# Z573_Holder_Mark1.net
KiCad netlist of a schematic drawn in EAGLE
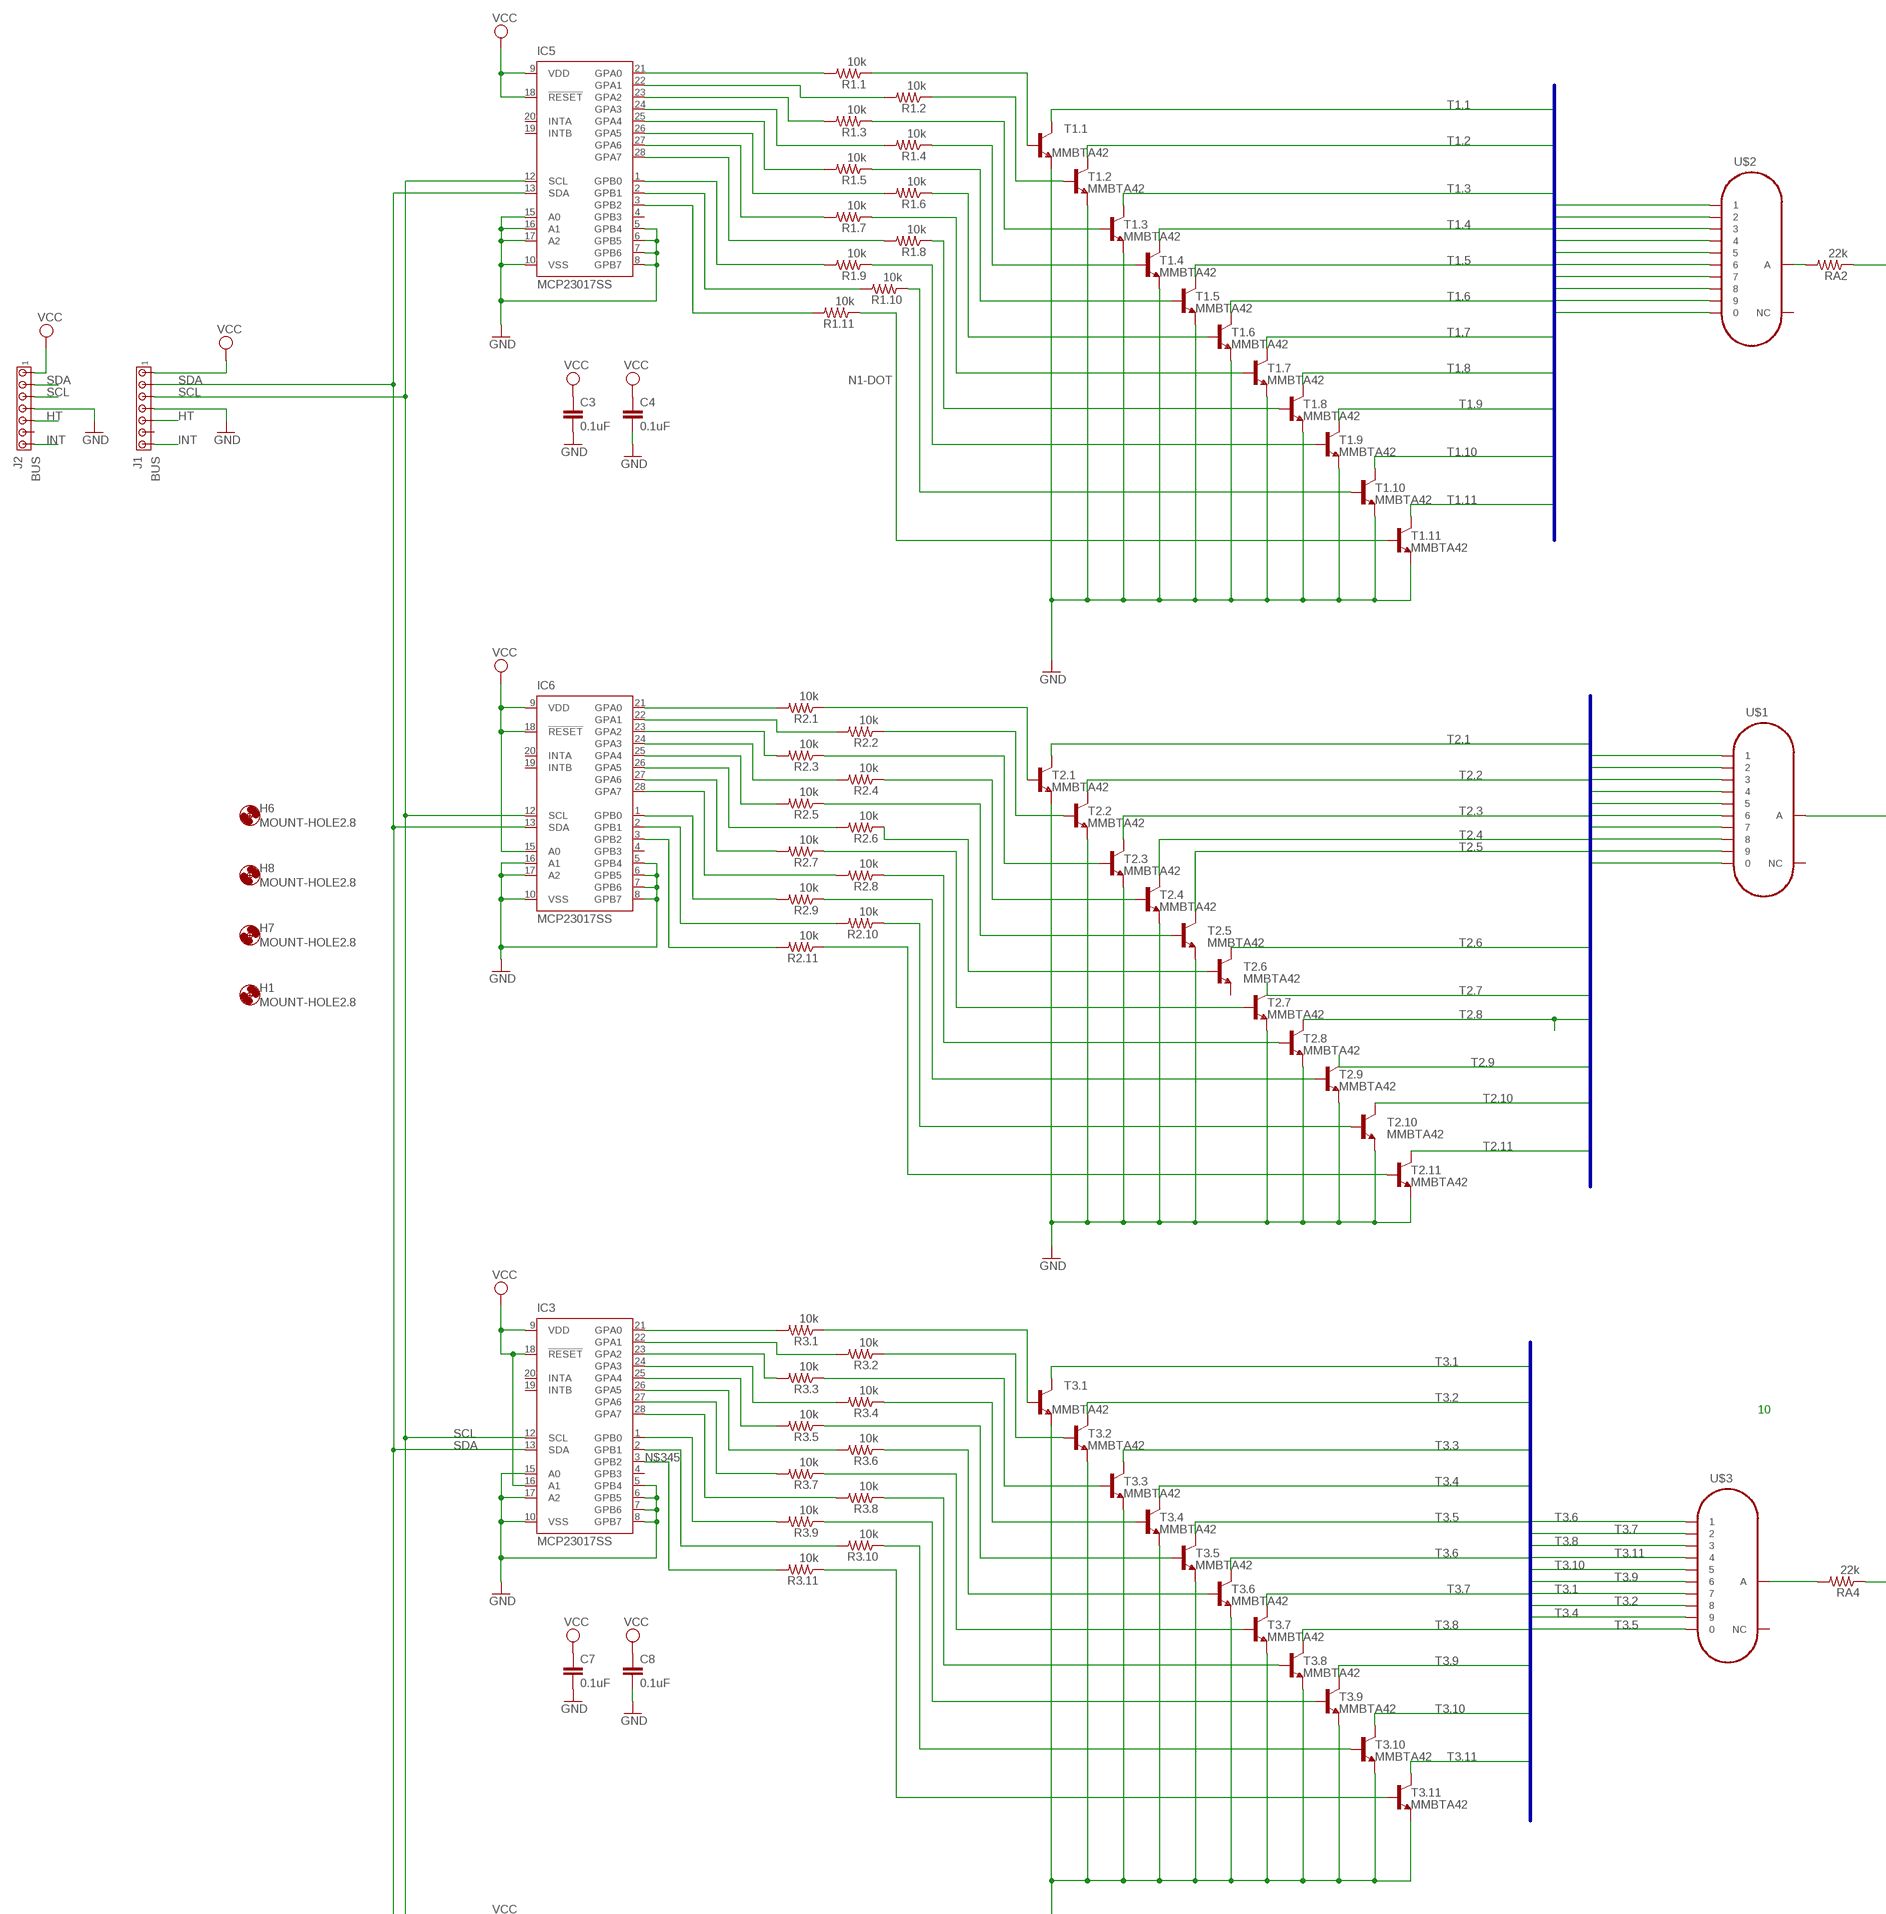
[diagram p0: schematic, sheet 1, part 1 of 3]
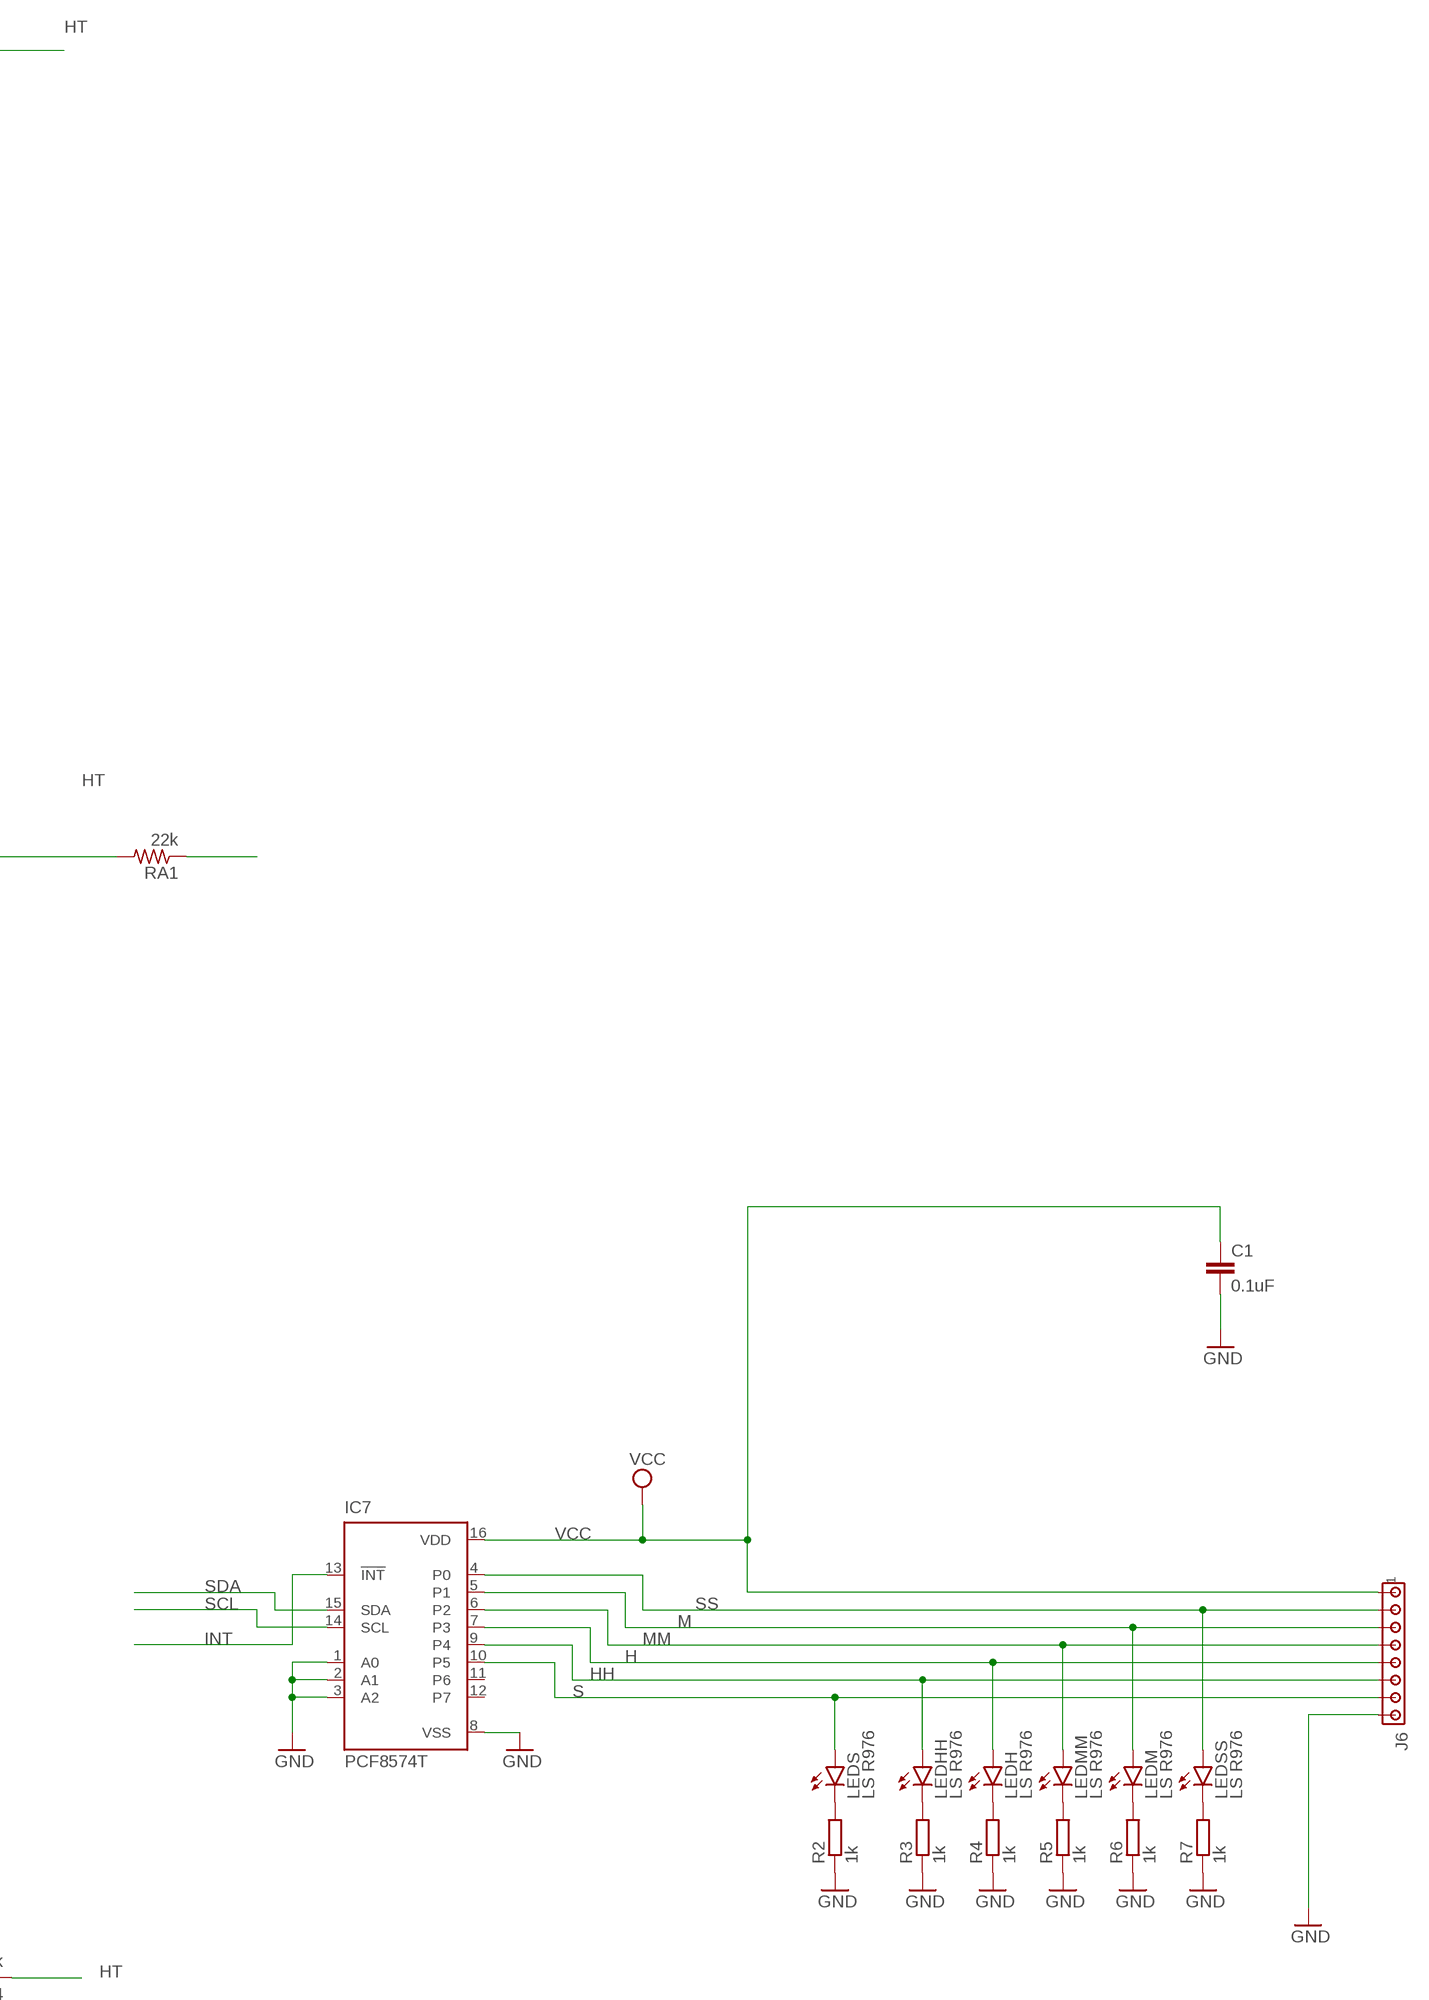
[diagram p1: schematic, sheet 1, part 2 of 3]
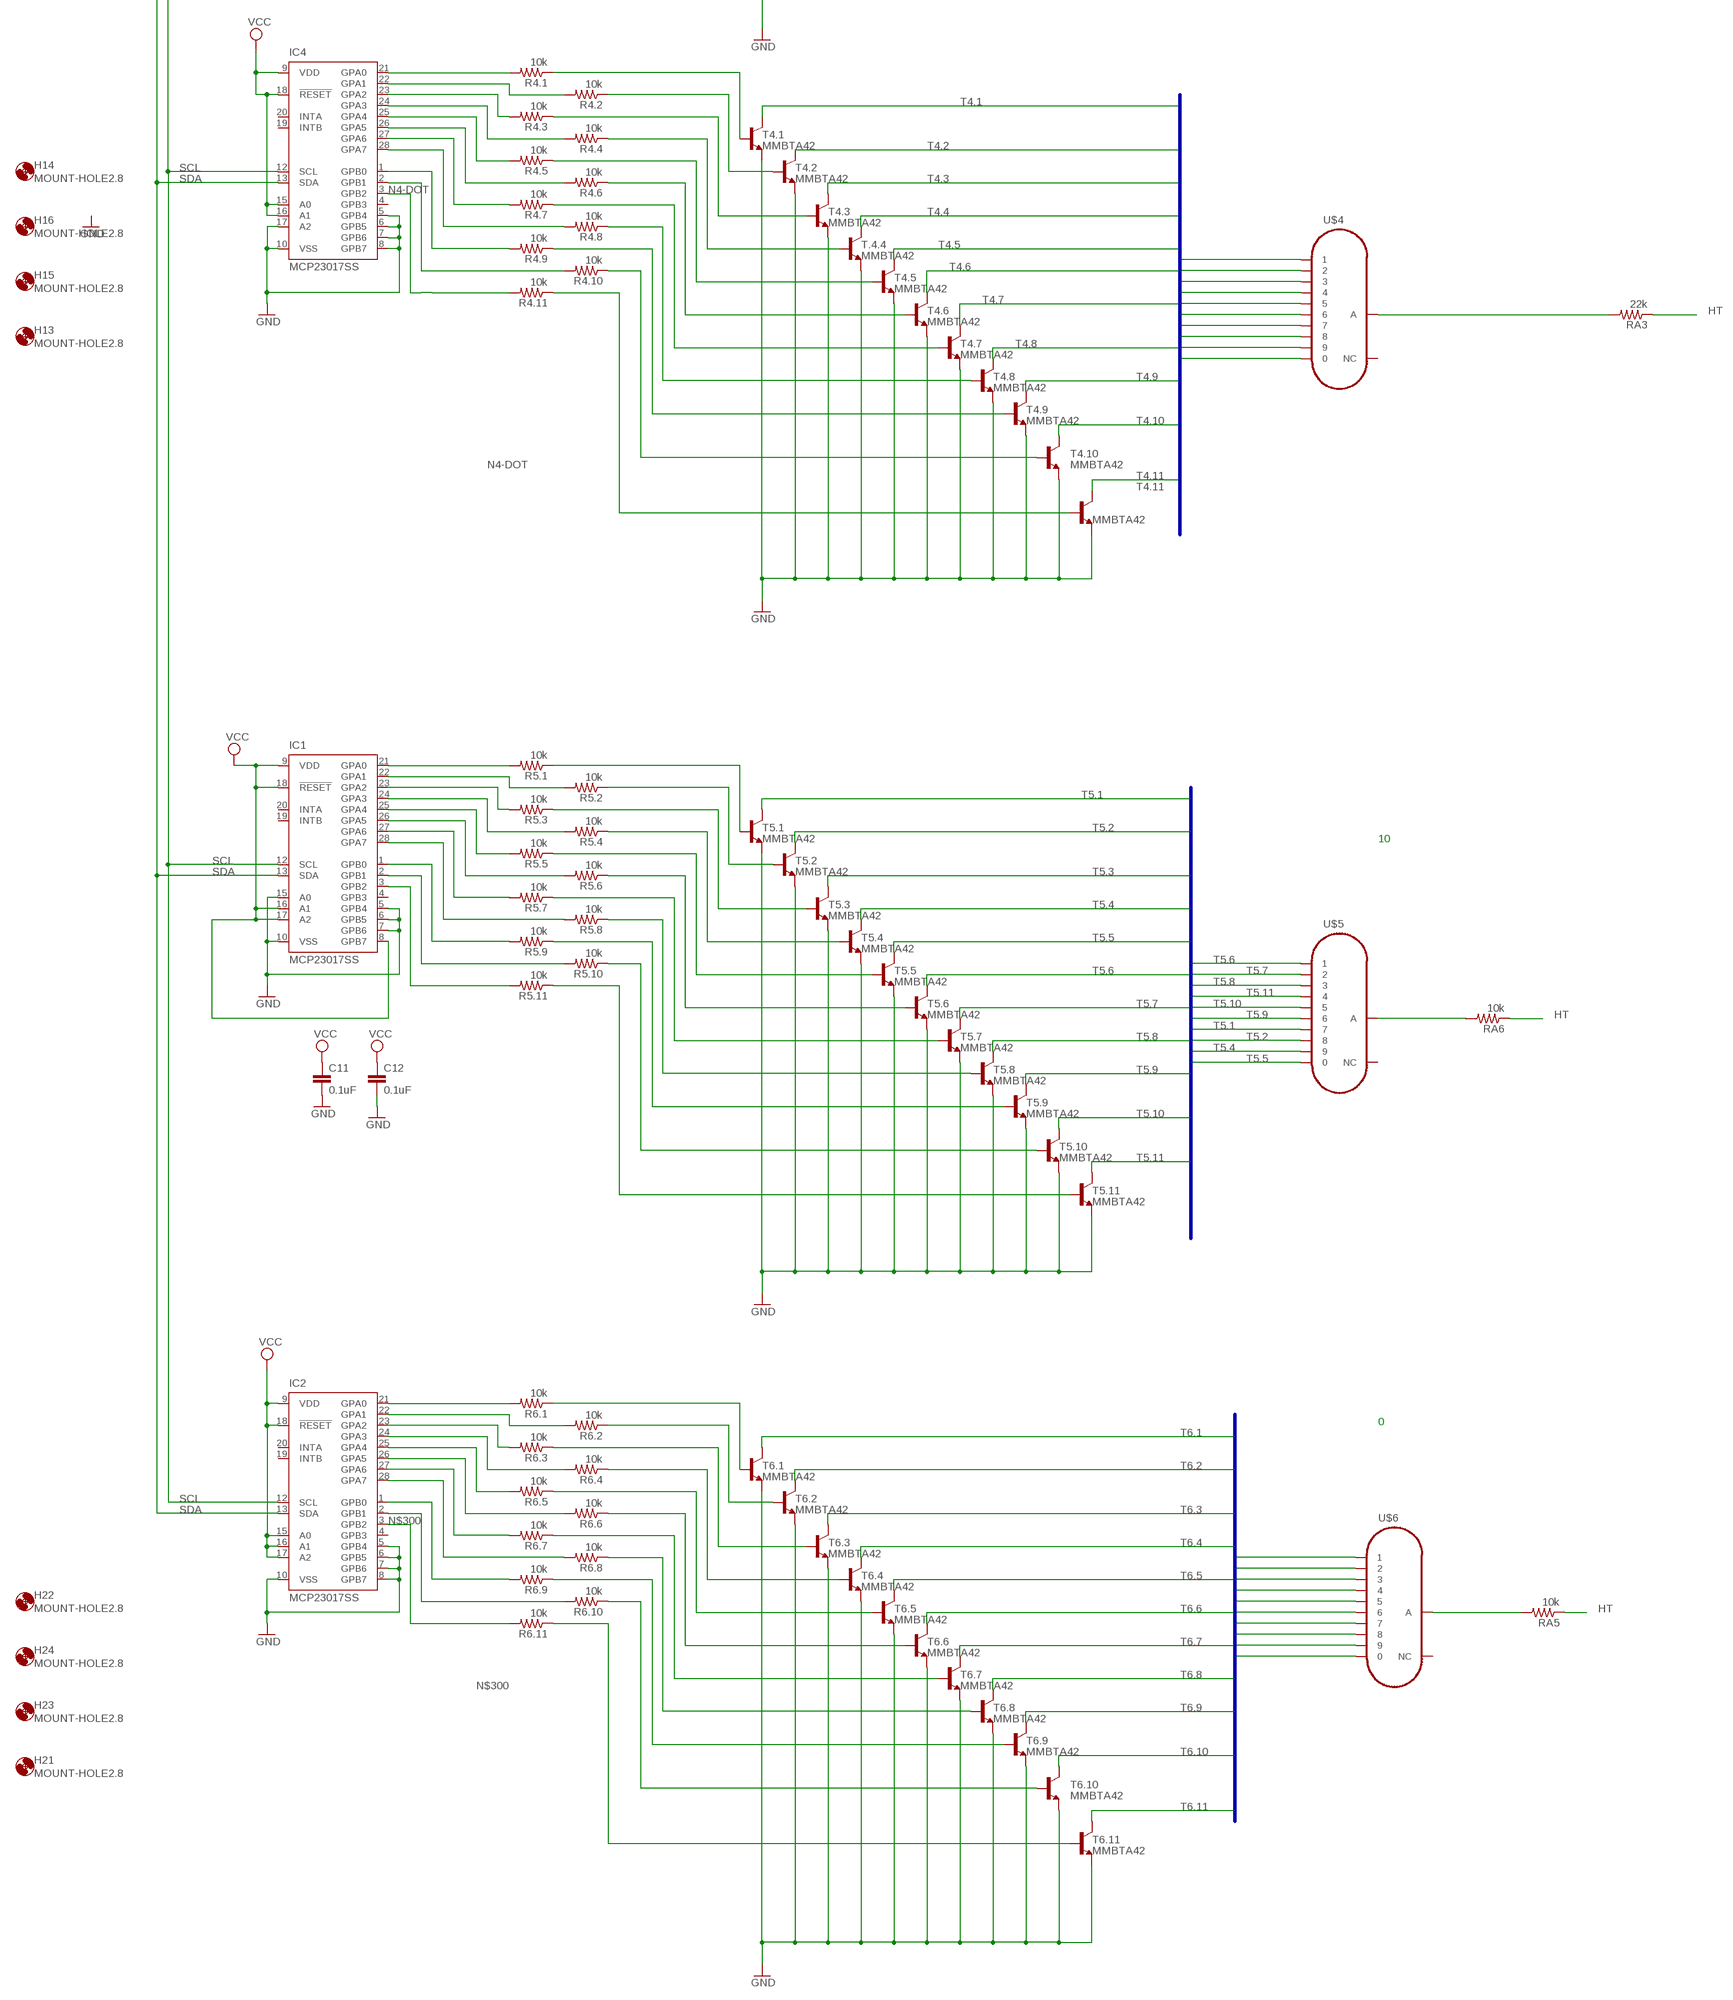
[diagram p2: schematic, sheet 1, part 3 of 3]

(export (version "E")
  (design (tool "Eeschema 10.0.6"))
  (components
    (comp (ref "C1")
      (value "0.1uF")
      (footprint "eagle-import:C0805")
      (libsource (lib "eagle-import") (part "C-EUC0805"))
    )
    (comp (ref "C3")
      (value "0.1uF")
      (footprint "eagle-import:C0805")
      (libsource (lib "eagle-import") (part "C-EUC0805"))
    )
    (comp (ref "C4")
      (value "0.1uF")
      (footprint "eagle-import:C0805")
      (libsource (lib "eagle-import") (part "C-EUC0805"))
    )
    (comp (ref "C7")
      (value "0.1uF")
      (footprint "eagle-import:C0805")
      (libsource (lib "eagle-import") (part "C-EUC0805"))
    )
    (comp (ref "C8")
      (value "0.1uF")
      (footprint "eagle-import:C0805")
      (libsource (lib "eagle-import") (part "C-EUC0805"))
    )
    (comp (ref "C11")
      (value "0.1uF")
      (footprint "eagle-import:C0805")
      (libsource (lib "eagle-import") (part "C-EUC0805"))
    )
    (comp (ref "C12")
      (value "0.1uF")
      (footprint "eagle-import:C0805")
      (libsource (lib "eagle-import") (part "C-EUC0805"))
    )
    (comp (ref "H1")
      (value "MOUNT-HOLE2.8")
      (footprint "eagle-import:2,8")
      (libsource (lib "eagle-import") (part "MOUNT-HOLE2.8"))
    )
    (comp (ref "H6")
      (value "MOUNT-HOLE2.8")
      (footprint "eagle-import:2,8")
      (libsource (lib "eagle-import") (part "MOUNT-HOLE2.8"))
    )
    (comp (ref "H7")
      (value "MOUNT-HOLE2.8")
      (footprint "eagle-import:2,8")
      (libsource (lib "eagle-import") (part "MOUNT-HOLE2.8"))
    )
    (comp (ref "H8")
      (value "MOUNT-HOLE2.8")
      (footprint "eagle-import:2,8")
      (libsource (lib "eagle-import") (part "MOUNT-HOLE2.8"))
    )
    (comp (ref "H13")
      (value "MOUNT-HOLE2.8")
      (footprint "eagle-import:2,8")
      (libsource (lib "eagle-import") (part "MOUNT-HOLE2.8"))
    )
    (comp (ref "H14")
      (value "MOUNT-HOLE2.8")
      (footprint "eagle-import:2,8")
      (libsource (lib "eagle-import") (part "MOUNT-HOLE2.8"))
    )
    (comp (ref "H15")
      (value "MOUNT-HOLE2.8")
      (footprint "eagle-import:2,8")
      (libsource (lib "eagle-import") (part "MOUNT-HOLE2.8"))
    )
    (comp (ref "H16")
      (value "MOUNT-HOLE2.8")
      (footprint "eagle-import:2,8")
      (libsource (lib "eagle-import") (part "MOUNT-HOLE2.8"))
    )
    (comp (ref "H21")
      (value "MOUNT-HOLE2.8")
      (footprint "eagle-import:2,8")
      (libsource (lib "eagle-import") (part "MOUNT-HOLE2.8"))
    )
    (comp (ref "H22")
      (value "MOUNT-HOLE2.8")
      (footprint "eagle-import:2,8")
      (libsource (lib "eagle-import") (part "MOUNT-HOLE2.8"))
    )
    (comp (ref "H23")
      (value "MOUNT-HOLE2.8")
      (footprint "eagle-import:2,8")
      (libsource (lib "eagle-import") (part "MOUNT-HOLE2.8"))
    )
    (comp (ref "H24")
      (value "MOUNT-HOLE2.8")
      (footprint "eagle-import:2,8")
      (libsource (lib "eagle-import") (part "MOUNT-HOLE2.8"))
    )
    (comp (ref "IC1")
      (value "MCP23017SS")
      (footprint "eagle-import:SSOP28")
      (libsource (lib "eagle-import") (part "MCP23017SS"))
    )
    (comp (ref "IC2")
      (value "MCP23017SS")
      (footprint "eagle-import:SSOP28")
      (libsource (lib "eagle-import") (part "MCP23017SS"))
    )
    (comp (ref "IC3")
      (value "MCP23017SS")
      (footprint "eagle-import:SSOP28")
      (libsource (lib "eagle-import") (part "MCP23017SS"))
    )
    (comp (ref "IC4")
      (value "MCP23017SS")
      (footprint "eagle-import:SSOP28")
      (libsource (lib "eagle-import") (part "MCP23017SS"))
    )
    (comp (ref "IC5")
      (value "MCP23017SS")
      (footprint "eagle-import:SSOP28")
      (libsource (lib "eagle-import") (part "MCP23017SS"))
    )
    (comp (ref "IC6")
      (value "MCP23017SS")
      (footprint "eagle-import:SSOP28")
      (libsource (lib "eagle-import") (part "MCP23017SS"))
    )
    (comp (ref "IC7")
      (value "PCF8574T")
      (footprint "eagle-import:SO16W")
      (fields (field (name "MPN") "PCF8574T/3,512"))
      (libsource (lib "eagle-import") (part "PCF8574T"))
    )
    (comp (ref "J1")
      (value "BUS")
      (footprint "eagle-import:10X07MTA")
      (libsource (lib "eagle-import") (part "MTA07-100"))
    )
    (comp (ref "J2")
      (value "BUS")
      (footprint "eagle-import:10X07MTA")
      (libsource (lib "eagle-import") (part "MTA07-100"))
    )
    (comp (ref "J6")
      (value "MTA08-100")
      (footprint "eagle-import:10X08MTA")
      (libsource (lib "eagle-import") (part "MTA08-100"))
    )
    (comp (ref "LEDH")
      (value "LS R976")
      (footprint "eagle-import:SML0805")
      (libsource (lib "eagle-import") (part "LEDSML0805"))
    )
    (comp (ref "LEDHH")
      (value "LS R976")
      (footprint "eagle-import:SML0805")
      (libsource (lib "eagle-import") (part "LEDSML0805"))
    )
    (comp (ref "LEDM")
      (value "LS R976")
      (footprint "eagle-import:SML0805")
      (libsource (lib "eagle-import") (part "LEDSML0805"))
    )
    (comp (ref "LEDMM")
      (value "LS R976")
      (footprint "eagle-import:SML0805")
      (libsource (lib "eagle-import") (part "LEDSML0805"))
    )
    (comp (ref "LEDS")
      (value "LS R976")
      (footprint "eagle-import:SML0805")
      (libsource (lib "eagle-import") (part "LEDSML0805"))
    )
    (comp (ref "LEDSS")
      (value "LS R976")
      (footprint "eagle-import:SML0805")
      (libsource (lib "eagle-import") (part "LEDSML0805"))
    )
    (comp (ref "R1.1")
      (value "10k")
      (footprint "eagle-import:R0603")
      (libsource (lib "eagle-import") (part "R-US_R0603"))
    )
    (comp (ref "R1.2")
      (value "10k")
      (footprint "eagle-import:R0603")
      (libsource (lib "eagle-import") (part "R-US_R0603"))
    )
    (comp (ref "R1.3")
      (value "10k")
      (footprint "eagle-import:R0603")
      (libsource (lib "eagle-import") (part "R-US_R0603"))
    )
    (comp (ref "R1.4")
      (value "10k")
      (footprint "eagle-import:R0603")
      (libsource (lib "eagle-import") (part "R-US_R0603"))
    )
    (comp (ref "R1.5")
      (value "10k")
      (footprint "eagle-import:R0603")
      (libsource (lib "eagle-import") (part "R-US_R0603"))
    )
    (comp (ref "R1.6")
      (value "10k")
      (footprint "eagle-import:R0603")
      (libsource (lib "eagle-import") (part "R-US_R0603"))
    )
    (comp (ref "R1.7")
      (value "10k")
      (footprint "eagle-import:R0603")
      (libsource (lib "eagle-import") (part "R-US_R0603"))
    )
    (comp (ref "R1.8")
      (value "10k")
      (footprint "eagle-import:R0603")
      (libsource (lib "eagle-import") (part "R-US_R0603"))
    )
    (comp (ref "R1.9")
      (value "10k")
      (footprint "eagle-import:R0603")
      (libsource (lib "eagle-import") (part "R-US_R0603"))
    )
    (comp (ref "R1.10")
      (value "10k")
      (footprint "eagle-import:R0603")
      (libsource (lib "eagle-import") (part "R-US_R0603"))
    )
    (comp (ref "R1.11")
      (value "10k")
      (footprint "eagle-import:R0603")
      (libsource (lib "eagle-import") (part "R-US_R0603"))
    )
    (comp (ref "R2")
      (value "1k")
      (footprint "eagle-import:R0805")
      (libsource (lib "eagle-import") (part "R-EU_R0805"))
    )
    (comp (ref "R2.1")
      (value "10k")
      (footprint "eagle-import:R0603")
      (libsource (lib "eagle-import") (part "R-US_R0603"))
    )
    (comp (ref "R2.2")
      (value "10k")
      (footprint "eagle-import:R0603")
      (libsource (lib "eagle-import") (part "R-US_R0603"))
    )
    (comp (ref "R2.3")
      (value "10k")
      (footprint "eagle-import:R0603")
      (libsource (lib "eagle-import") (part "R-US_R0603"))
    )
    (comp (ref "R2.4")
      (value "10k")
      (footprint "eagle-import:R0603")
      (libsource (lib "eagle-import") (part "R-US_R0603"))
    )
    (comp (ref "R2.5")
      (value "10k")
      (footprint "eagle-import:R0603")
      (libsource (lib "eagle-import") (part "R-US_R0603"))
    )
    (comp (ref "R2.6")
      (value "10k")
      (footprint "eagle-import:R0603")
      (libsource (lib "eagle-import") (part "R-US_R0603"))
    )
    (comp (ref "R2.7")
      (value "10k")
      (footprint "eagle-import:R0603")
      (libsource (lib "eagle-import") (part "R-US_R0603"))
    )
    (comp (ref "R2.8")
      (value "10k")
      (footprint "eagle-import:R0603")
      (libsource (lib "eagle-import") (part "R-US_R0603"))
    )
    (comp (ref "R2.9")
      (value "10k")
      (footprint "eagle-import:R0603")
      (libsource (lib "eagle-import") (part "R-US_R0603"))
    )
    (comp (ref "R2.10")
      (value "10k")
      (footprint "eagle-import:R0603")
      (libsource (lib "eagle-import") (part "R-US_R0603"))
    )
    (comp (ref "R2.11")
      (value "10k")
      (footprint "eagle-import:R0603")
      (libsource (lib "eagle-import") (part "R-US_R0603"))
    )
    (comp (ref "R3")
      (value "1k")
      (footprint "eagle-import:R0805")
      (libsource (lib "eagle-import") (part "R-EU_R0805"))
    )
    (comp (ref "R3.1")
      (value "10k")
      (footprint "eagle-import:R0603")
      (libsource (lib "eagle-import") (part "R-US_R0603"))
    )
    (comp (ref "R3.2")
      (value "10k")
      (footprint "eagle-import:R0603")
      (libsource (lib "eagle-import") (part "R-US_R0603"))
    )
    (comp (ref "R3.3")
      (value "10k")
      (footprint "eagle-import:R0603")
      (libsource (lib "eagle-import") (part "R-US_R0603"))
    )
    (comp (ref "R3.4")
      (value "10k")
      (footprint "eagle-import:R0603")
      (libsource (lib "eagle-import") (part "R-US_R0603"))
    )
    (comp (ref "R3.5")
      (value "10k")
      (footprint "eagle-import:R0603")
      (libsource (lib "eagle-import") (part "R-US_R0603"))
    )
    (comp (ref "R3.6")
      (value "10k")
      (footprint "eagle-import:R0603")
      (libsource (lib "eagle-import") (part "R-US_R0603"))
    )
    (comp (ref "R3.7")
      (value "10k")
      (footprint "eagle-import:R0603")
      (libsource (lib "eagle-import") (part "R-US_R0603"))
    )
    (comp (ref "R3.8")
      (value "10k")
      (footprint "eagle-import:R0603")
      (libsource (lib "eagle-import") (part "R-US_R0603"))
    )
    (comp (ref "R3.9")
      (value "10k")
      (footprint "eagle-import:R0603")
      (libsource (lib "eagle-import") (part "R-US_R0603"))
    )
    (comp (ref "R3.10")
      (value "10k")
      (footprint "eagle-import:R0603")
      (libsource (lib "eagle-import") (part "R-US_R0603"))
    )
    (comp (ref "R3.11")
      (value "10k")
      (footprint "eagle-import:R0603")
      (libsource (lib "eagle-import") (part "R-US_R0603"))
    )
    (comp (ref "R4")
      (value "1k")
      (footprint "eagle-import:R0805")
      (libsource (lib "eagle-import") (part "R-EU_R0805"))
    )
    (comp (ref "R4.1")
      (value "10k")
      (footprint "eagle-import:R0603")
      (libsource (lib "eagle-import") (part "R-US_R0603"))
    )
    (comp (ref "R4.2")
      (value "10k")
      (footprint "eagle-import:R0603")
      (libsource (lib "eagle-import") (part "R-US_R0603"))
    )
    (comp (ref "R4.3")
      (value "10k")
      (footprint "eagle-import:R0603")
      (libsource (lib "eagle-import") (part "R-US_R0603"))
    )
    (comp (ref "R4.4")
      (value "10k")
      (footprint "eagle-import:R0603")
      (libsource (lib "eagle-import") (part "R-US_R0603"))
    )
    (comp (ref "R4.5")
      (value "10k")
      (footprint "eagle-import:R0603")
      (libsource (lib "eagle-import") (part "R-US_R0603"))
    )
    (comp (ref "R4.6")
      (value "10k")
      (footprint "eagle-import:R0603")
      (libsource (lib "eagle-import") (part "R-US_R0603"))
    )
    (comp (ref "R4.7")
      (value "10k")
      (footprint "eagle-import:R0603")
      (libsource (lib "eagle-import") (part "R-US_R0603"))
    )
    (comp (ref "R4.8")
      (value "10k")
      (footprint "eagle-import:R0603")
      (libsource (lib "eagle-import") (part "R-US_R0603"))
    )
    (comp (ref "R4.9")
      (value "10k")
      (footprint "eagle-import:R0603")
      (libsource (lib "eagle-import") (part "R-US_R0603"))
    )
    (comp (ref "R4.10")
      (value "10k")
      (footprint "eagle-import:R0603")
      (libsource (lib "eagle-import") (part "R-US_R0603"))
    )
    (comp (ref "R4.11")
      (value "10k")
      (footprint "eagle-import:R0603")
      (libsource (lib "eagle-import") (part "R-US_R0603"))
    )
    (comp (ref "R5")
      (value "1k")
      (footprint "eagle-import:R0805")
      (libsource (lib "eagle-import") (part "R-EU_R0805"))
    )
    (comp (ref "R5.1")
      (value "10k")
      (footprint "eagle-import:R0603")
      (libsource (lib "eagle-import") (part "R-US_R0603"))
    )
    (comp (ref "R5.2")
      (value "10k")
      (footprint "eagle-import:R0603")
      (libsource (lib "eagle-import") (part "R-US_R0603"))
    )
    (comp (ref "R5.3")
      (value "10k")
      (footprint "eagle-import:R0603")
      (libsource (lib "eagle-import") (part "R-US_R0603"))
    )
    (comp (ref "R5.4")
      (value "10k")
      (footprint "eagle-import:R0603")
      (libsource (lib "eagle-import") (part "R-US_R0603"))
    )
    (comp (ref "R5.5")
      (value "10k")
      (footprint "eagle-import:R0603")
      (libsource (lib "eagle-import") (part "R-US_R0603"))
    )
    (comp (ref "R5.6")
      (value "10k")
      (footprint "eagle-import:R0603")
      (libsource (lib "eagle-import") (part "R-US_R0603"))
    )
    (comp (ref "R5.7")
      (value "10k")
      (footprint "eagle-import:R0603")
      (libsource (lib "eagle-import") (part "R-US_R0603"))
    )
    (comp (ref "R5.8")
      (value "10k")
      (footprint "eagle-import:R0603")
      (libsource (lib "eagle-import") (part "R-US_R0603"))
    )
    (comp (ref "R5.9")
      (value "10k")
      (footprint "eagle-import:R0603")
      (libsource (lib "eagle-import") (part "R-US_R0603"))
    )
    (comp (ref "R5.10")
      (value "10k")
      (footprint "eagle-import:R0603")
      (libsource (lib "eagle-import") (part "R-US_R0603"))
    )
    (comp (ref "R5.11")
      (value "10k")
      (footprint "eagle-import:R0603")
      (libsource (lib "eagle-import") (part "R-US_R0603"))
    )
    (comp (ref "R6")
      (value "1k")
      (footprint "eagle-import:R0805")
      (libsource (lib "eagle-import") (part "R-EU_R0805"))
    )
    (comp (ref "R6.1")
      (value "10k")
      (footprint "eagle-import:R0603")
      (libsource (lib "eagle-import") (part "R-US_R0603"))
    )
    (comp (ref "R6.2")
      (value "10k")
      (footprint "eagle-import:R0603")
      (libsource (lib "eagle-import") (part "R-US_R0603"))
    )
    (comp (ref "R6.3")
      (value "10k")
      (footprint "eagle-import:R0603")
      (libsource (lib "eagle-import") (part "R-US_R0603"))
    )
    (comp (ref "R6.4")
      (value "10k")
      (footprint "eagle-import:R0603")
      (libsource (lib "eagle-import") (part "R-US_R0603"))
    )
    (comp (ref "R6.5")
      (value "10k")
      (footprint "eagle-import:R0603")
      (libsource (lib "eagle-import") (part "R-US_R0603"))
    )
    (comp (ref "R6.6")
      (value "10k")
      (footprint "eagle-import:R0603")
      (libsource (lib "eagle-import") (part "R-US_R0603"))
    )
    (comp (ref "R6.7")
      (value "10k")
      (footprint "eagle-import:R0603")
      (libsource (lib "eagle-import") (part "R-US_R0603"))
    )
    (comp (ref "R6.8")
      (value "10k")
      (footprint "eagle-import:R0603")
      (libsource (lib "eagle-import") (part "R-US_R0603"))
    )
    (comp (ref "R6.9")
      (value "10k")
      (footprint "eagle-import:R0603")
      (libsource (lib "eagle-import") (part "R-US_R0603"))
    )
    (comp (ref "R6.10")
      (value "10k")
      (footprint "eagle-import:R0603")
      (libsource (lib "eagle-import") (part "R-US_R0603"))
    )
    (comp (ref "R6.11")
      (value "10k")
      (footprint "eagle-import:R0603")
      (libsource (lib "eagle-import") (part "R-US_R0603"))
    )
    (comp (ref "R7")
      (value "1k")
      (footprint "eagle-import:R0805")
      (libsource (lib "eagle-import") (part "R-EU_R0805"))
    )
    (comp (ref "RA1")
      (value "22k")
      (footprint "eagle-import:M0805")
      (libsource (lib "eagle-import") (part "R-US_M0805"))
    )
    (comp (ref "RA2")
      (value "22k")
      (footprint "eagle-import:M0805")
      (libsource (lib "eagle-import") (part "R-US_M0805"))
    )
    (comp (ref "RA3")
      (value "22k")
      (footprint "eagle-import:M0805")
      (libsource (lib "eagle-import") (part "R-US_M0805"))
    )
    (comp (ref "RA4")
      (value "22k")
      (footprint "eagle-import:M0805")
      (libsource (lib "eagle-import") (part "R-US_M0805"))
    )
    (comp (ref "RA5")
      (value "10k")
      (footprint "eagle-import:M0805")
      (libsource (lib "eagle-import") (part "R-US_M0805"))
    )
    (comp (ref "RA6")
      (value "10k")
      (footprint "eagle-import:M0805")
      (libsource (lib "eagle-import") (part "R-US_M0805"))
    )
    (comp (ref "T.4.4")
      (value "MMBTA42")
      (footprint "eagle-import:SOT23")
      (libsource (lib "eagle-import") (part "BC846"))
    )
    (comp (ref "T1.1")
      (value "MMBTA42")
      (footprint "eagle-import:SOT23")
      (libsource (lib "eagle-import") (part "BC846"))
    )
    (comp (ref "T1.2")
      (value "MMBTA42")
      (footprint "eagle-import:SOT23")
      (libsource (lib "eagle-import") (part "BC846"))
    )
    (comp (ref "T1.3")
      (value "MMBTA42")
      (footprint "eagle-import:SOT23")
      (libsource (lib "eagle-import") (part "BC846"))
    )
    (comp (ref "T1.4")
      (value "MMBTA42")
      (footprint "eagle-import:SOT23")
      (libsource (lib "eagle-import") (part "BC846"))
    )
    (comp (ref "T1.5")
      (value "MMBTA42")
      (footprint "eagle-import:SOT23")
      (libsource (lib "eagle-import") (part "BC846"))
    )
    (comp (ref "T1.6")
      (value "MMBTA42")
      (footprint "eagle-import:SOT23")
      (libsource (lib "eagle-import") (part "BC846"))
    )
    (comp (ref "T1.7")
      (value "MMBTA42")
      (footprint "eagle-import:SOT23")
      (libsource (lib "eagle-import") (part "BC846"))
    )
    (comp (ref "T1.8")
      (value "MMBTA42")
      (footprint "eagle-import:SOT23")
      (libsource (lib "eagle-import") (part "BC846"))
    )
    (comp (ref "T1.9")
      (value "MMBTA42")
      (footprint "eagle-import:SOT23")
      (libsource (lib "eagle-import") (part "BC846"))
    )
    (comp (ref "T1.10")
      (value "MMBTA42")
      (footprint "eagle-import:SOT23")
      (libsource (lib "eagle-import") (part "BC846"))
    )
    (comp (ref "T1.11")
      (value "MMBTA42")
      (footprint "eagle-import:SOT23")
      (libsource (lib "eagle-import") (part "BC846"))
    )
    (comp (ref "T2.1")
      (value "MMBTA42")
      (footprint "eagle-import:SOT23")
      (libsource (lib "eagle-import") (part "BC846"))
    )
    (comp (ref "T2.2")
      (value "MMBTA42")
      (footprint "eagle-import:SOT23")
      (libsource (lib "eagle-import") (part "BC846"))
    )
    (comp (ref "T2.3")
      (value "MMBTA42")
      (footprint "eagle-import:SOT23")
      (libsource (lib "eagle-import") (part "BC846"))
    )
    (comp (ref "T2.4")
      (value "MMBTA42")
      (footprint "eagle-import:SOT23")
      (libsource (lib "eagle-import") (part "BC846"))
    )
    (comp (ref "T2.5")
      (value "MMBTA42")
      (footprint "eagle-import:SOT23")
      (libsource (lib "eagle-import") (part "BC846"))
    )
    (comp (ref "T2.6")
      (value "MMBTA42")
      (footprint "eagle-import:SOT23")
      (libsource (lib "eagle-import") (part "BC846"))
    )
    (comp (ref "T2.7")
      (value "MMBTA42")
      (footprint "eagle-import:SOT23")
      (libsource (lib "eagle-import") (part "BC846"))
    )
    (comp (ref "T2.8")
      (value "MMBTA42")
      (footprint "eagle-import:SOT23")
      (libsource (lib "eagle-import") (part "BC846"))
    )
    (comp (ref "T2.9")
      (value "MMBTA42")
      (footprint "eagle-import:SOT23")
      (libsource (lib "eagle-import") (part "BC846"))
    )
    (comp (ref "T2.10")
      (value "MMBTA42")
      (footprint "eagle-import:SOT23")
      (libsource (lib "eagle-import") (part "BC846"))
    )
    (comp (ref "T2.11")
      (value "MMBTA42")
      (footprint "eagle-import:SOT23")
      (libsource (lib "eagle-import") (part "BC846"))
    )
    (comp (ref "T3.1")
      (value "MMBTA42")
      (footprint "eagle-import:SOT23")
      (libsource (lib "eagle-import") (part "BC846"))
    )
    (comp (ref "T3.2")
      (value "MMBTA42")
      (footprint "eagle-import:SOT23")
      (libsource (lib "eagle-import") (part "BC846"))
    )
    (comp (ref "T3.3")
      (value "MMBTA42")
      (footprint "eagle-import:SOT23")
      (libsource (lib "eagle-import") (part "BC846"))
    )
    (comp (ref "T3.4")
      (value "MMBTA42")
      (footprint "eagle-import:SOT23")
      (libsource (lib "eagle-import") (part "BC846"))
    )
    (comp (ref "T3.5")
      (value "MMBTA42")
      (footprint "eagle-import:SOT23")
      (libsource (lib "eagle-import") (part "BC846"))
    )
    (comp (ref "T3.6")
      (value "MMBTA42")
      (footprint "eagle-import:SOT23")
      (libsource (lib "eagle-import") (part "BC846"))
    )
    (comp (ref "T3.7")
      (value "MMBTA42")
      (footprint "eagle-import:SOT23")
      (libsource (lib "eagle-import") (part "BC846"))
    )
    (comp (ref "T3.8")
      (value "MMBTA42")
      (footprint "eagle-import:SOT23")
      (libsource (lib "eagle-import") (part "BC846"))
    )
    (comp (ref "T3.9")
      (value "MMBTA42")
      (footprint "eagle-import:SOT23")
      (libsource (lib "eagle-import") (part "BC846"))
    )
    (comp (ref "T3.10")
      (value "MMBTA42")
      (footprint "eagle-import:SOT23")
      (libsource (lib "eagle-import") (part "BC846"))
    )
    (comp (ref "T3.11")
      (value "MMBTA42")
      (footprint "eagle-import:SOT23")
      (libsource (lib "eagle-import") (part "BC846"))
    )
    (comp (ref "T4.1")
      (value "MMBTA42")
      (footprint "eagle-import:SOT23")
      (libsource (lib "eagle-import") (part "BC846"))
    )
    (comp (ref "T4.2")
      (value "MMBTA42")
      (footprint "eagle-import:SOT23")
      (libsource (lib "eagle-import") (part "BC846"))
    )
    (comp (ref "T4.3")
      (value "MMBTA42")
      (footprint "eagle-import:SOT23")
      (libsource (lib "eagle-import") (part "BC846"))
    )
    (comp (ref "T4.5")
      (value "MMBTA42")
      (footprint "eagle-import:SOT23")
      (libsource (lib "eagle-import") (part "BC846"))
    )
    (comp (ref "T4.6")
      (value "MMBTA42")
      (footprint "eagle-import:SOT23")
      (libsource (lib "eagle-import") (part "BC846"))
    )
    (comp (ref "T4.7")
      (value "MMBTA42")
      (footprint "eagle-import:SOT23")
      (libsource (lib "eagle-import") (part "BC846"))
    )
    (comp (ref "T4.8")
      (value "MMBTA42")
      (footprint "eagle-import:SOT23")
      (libsource (lib "eagle-import") (part "BC846"))
    )
    (comp (ref "T4.9")
      (value "MMBTA42")
      (footprint "eagle-import:SOT23")
      (libsource (lib "eagle-import") (part "BC846"))
    )
    (comp (ref "T4.10")
      (value "MMBTA42")
      (footprint "eagle-import:SOT23")
      (libsource (lib "eagle-import") (part "BC846"))
    )
    (comp (ref "T4.11")
      (value "MMBTA42")
      (footprint "eagle-import:SOT23")
      (libsource (lib "eagle-import") (part "BC846"))
    )
    (comp (ref "T5.1")
      (value "MMBTA42")
      (footprint "eagle-import:SOT23")
      (libsource (lib "eagle-import") (part "BC846"))
    )
    (comp (ref "T5.2")
      (value "MMBTA42")
      (footprint "eagle-import:SOT23")
      (libsource (lib "eagle-import") (part "BC846"))
    )
    (comp (ref "T5.3")
      (value "MMBTA42")
      (footprint "eagle-import:SOT23")
      (libsource (lib "eagle-import") (part "BC846"))
    )
    (comp (ref "T5.4")
      (value "MMBTA42")
      (footprint "eagle-import:SOT23")
      (libsource (lib "eagle-import") (part "BC846"))
    )
    (comp (ref "T5.5")
      (value "MMBTA42")
      (footprint "eagle-import:SOT23")
      (libsource (lib "eagle-import") (part "BC846"))
    )
    (comp (ref "T5.6")
      (value "MMBTA42")
      (footprint "eagle-import:SOT23")
      (libsource (lib "eagle-import") (part "BC846"))
    )
    (comp (ref "T5.7")
      (value "MMBTA42")
      (footprint "eagle-import:SOT23")
      (libsource (lib "eagle-import") (part "BC846"))
    )
    (comp (ref "T5.8")
      (value "MMBTA42")
      (footprint "eagle-import:SOT23")
      (libsource (lib "eagle-import") (part "BC846"))
    )
    (comp (ref "T5.9")
      (value "MMBTA42")
      (footprint "eagle-import:SOT23")
      (libsource (lib "eagle-import") (part "BC846"))
    )
    (comp (ref "T5.10")
      (value "MMBTA42")
      (footprint "eagle-import:SOT23")
      (libsource (lib "eagle-import") (part "BC846"))
    )
    (comp (ref "T5.11")
      (value "MMBTA42")
      (footprint "eagle-import:SOT23")
      (libsource (lib "eagle-import") (part "BC846"))
    )
    (comp (ref "T6.1")
      (value "MMBTA42")
      (footprint "eagle-import:SOT23")
      (libsource (lib "eagle-import") (part "BC846"))
    )
    (comp (ref "T6.2")
      (value "MMBTA42")
      (footprint "eagle-import:SOT23")
      (libsource (lib "eagle-import") (part "BC846"))
    )
    (comp (ref "T6.3")
      (value "MMBTA42")
      (footprint "eagle-import:SOT23")
      (libsource (lib "eagle-import") (part "BC846"))
    )
    (comp (ref "T6.4")
      (value "MMBTA42")
      (footprint "eagle-import:SOT23")
      (libsource (lib "eagle-import") (part "BC846"))
    )
    (comp (ref "T6.5")
      (value "MMBTA42")
      (footprint "eagle-import:SOT23")
      (libsource (lib "eagle-import") (part "BC846"))
    )
    (comp (ref "T6.6")
      (value "MMBTA42")
      (footprint "eagle-import:SOT23")
      (libsource (lib "eagle-import") (part "BC846"))
    )
    (comp (ref "T6.7")
      (value "MMBTA42")
      (footprint "eagle-import:SOT23")
      (libsource (lib "eagle-import") (part "BC846"))
    )
    (comp (ref "T6.8")
      (value "MMBTA42")
      (footprint "eagle-import:SOT23")
      (libsource (lib "eagle-import") (part "BC846"))
    )
    (comp (ref "T6.9")
      (value "MMBTA42")
      (footprint "eagle-import:SOT23")
      (libsource (lib "eagle-import") (part "BC846"))
    )
    (comp (ref "T6.10")
      (value "MMBTA42")
      (footprint "eagle-import:SOT23")
      (libsource (lib "eagle-import") (part "BC846"))
    )
    (comp (ref "T6.11")
      (value "MMBTA42")
      (footprint "eagle-import:SOT23")
      (libsource (lib "eagle-import") (part "BC846"))
    )
    (comp (ref "U$1")
      (value "Z573")
      (footprint "eagle-import:Z573M")
      (libsource (lib "eagle-import") (part "Z573"))
    )
    (comp (ref "U$2")
      (value "Z573")
      (footprint "eagle-import:Z573M")
      (libsource (lib "eagle-import") (part "Z573"))
    )
    (comp (ref "U$3")
      (value "Z573")
      (footprint "eagle-import:Z573M")
      (libsource (lib "eagle-import") (part "Z573"))
    )
    (comp (ref "U$4")
      (value "Z573")
      (footprint "eagle-import:Z573M")
      (libsource (lib "eagle-import") (part "Z573"))
    )
    (comp (ref "U$5")
      (value "Z573")
      (footprint "eagle-import:Z573M")
      (libsource (lib "eagle-import") (part "Z573"))
    )
    (comp (ref "U$6")
      (value "Z573")
      (footprint "eagle-import:Z573M")
      (libsource (lib "eagle-import") (part "Z573"))
    )
  )
  (nets
    (net (code "1") (name "/H") (class "Default")
      (node (ref "IC7") (pin "7") (pinfunction "P3_7") (pintype "bidirectional"))
      (node (ref "J6") (pin "5") (pinfunction "5_5") (pintype "passive"))
      (node (ref "LEDH") (pin "A") (pinfunction "A_A") (pintype "passive"))
    )
    (net (code "2") (name "/HH") (class "Default")
      (node (ref "IC7") (pin "9") (pinfunction "P4_9") (pintype "bidirectional"))
      (node (ref "J6") (pin "6") (pinfunction "6_6") (pintype "passive"))
      (node (ref "LEDHH") (pin "A") (pinfunction "A_A") (pintype "passive"))
    )
    (net (code "3") (name "/HT") (class "Default")
      (node (ref "J1") (pin "5") (pinfunction "5_5") (pintype "passive"))
      (node (ref "J2") (pin "5") (pinfunction "5_5") (pintype "passive"))
      (node (ref "RA1") (pin "1") (pinfunction "1_1") (pintype "passive"))
      (node (ref "RA2") (pin "1") (pinfunction "1_1") (pintype "passive"))
      (node (ref "RA3") (pin "1") (pinfunction "1_1") (pintype "passive"))
      (node (ref "RA4") (pin "1") (pinfunction "1_1") (pintype "passive"))
      (node (ref "RA5") (pin "1") (pinfunction "1_1") (pintype "passive"))
      (node (ref "RA6") (pin "1") (pinfunction "1_1") (pintype "passive"))
    )
    (net (code "4") (name "/INT") (class "Default")
      (node (ref "IC7") (pin "13") (pinfunction "~{INT}_13") (pintype "output"))
      (node (ref "J1") (pin "7") (pinfunction "7_7") (pintype "passive"))
      (node (ref "J2") (pin "7") (pinfunction "7_7") (pintype "passive"))
    )
    (net (code "5") (name "/M") (class "Default")
      (node (ref "IC7") (pin "5") (pinfunction "P1_5") (pintype "bidirectional"))
      (node (ref "J6") (pin "3") (pinfunction "3_3") (pintype "passive"))
      (node (ref "LEDM") (pin "A") (pinfunction "A_A") (pintype "passive"))
    )
    (net (code "6") (name "/MM") (class "Default")
      (node (ref "IC7") (pin "6") (pinfunction "P2_6") (pintype "bidirectional"))
      (node (ref "J6") (pin "4") (pinfunction "4_4") (pintype "passive"))
      (node (ref "LEDMM") (pin "A") (pinfunction "A_A") (pintype "passive"))
    )
    (net (code "7") (name "/N$300") (class "Default")
      (node (ref "IC2") (pin "3") (pinfunction "GPB2_3") (pintype "bidirectional"))
      (node (ref "R6.11") (pin "2") (pinfunction "2_2") (pintype "passive"))
    )
    (net (code "8") (name "/N$345") (class "Default")
      (node (ref "IC3") (pin "3") (pinfunction "GPB2_3") (pintype "bidirectional"))
      (node (ref "R3.11") (pin "2") (pinfunction "2_2") (pintype "passive"))
    )
    (net (code "9") (name "/N1-DOT") (class "Default")
      (node (ref "IC5") (pin "3") (pinfunction "GPB2_3") (pintype "bidirectional"))
      (node (ref "R1.11") (pin "2") (pinfunction "2_2") (pintype "passive"))
    )
    (net (code "10") (name "/N4-DOT") (class "Default")
      (node (ref "IC4") (pin "3") (pinfunction "GPB2_3") (pintype "bidirectional"))
      (node (ref "R4.11") (pin "2") (pinfunction "2_2") (pintype "passive"))
    )
    (net (code "11") (name "/S") (class "Default")
      (node (ref "IC7") (pin "10") (pinfunction "P5_10") (pintype "bidirectional"))
      (node (ref "J6") (pin "7") (pinfunction "7_7") (pintype "passive"))
      (node (ref "LEDS") (pin "A") (pinfunction "A_A") (pintype "passive"))
    )
    (net (code "12") (name "/SCL") (class "Default")
      (node (ref "IC1") (pin "12") (pinfunction "SCL_12") (pintype "input"))
      (node (ref "IC2") (pin "12") (pinfunction "SCL_12") (pintype "input"))
      (node (ref "IC3") (pin "12") (pinfunction "SCL_12") (pintype "input"))
      (node (ref "IC4") (pin "12") (pinfunction "SCL_12") (pintype "input"))
      (node (ref "IC5") (pin "12") (pinfunction "SCL_12") (pintype "input"))
      (node (ref "IC6") (pin "12") (pinfunction "SCL_12") (pintype "input"))
      (node (ref "IC7") (pin "14") (pinfunction "SCL_14") (pintype "input"))
      (node (ref "J1") (pin "3") (pinfunction "3_3") (pintype "passive"))
      (node (ref "J2") (pin "3") (pinfunction "3_3") (pintype "passive"))
    )
    (net (code "13") (name "/SDA") (class "Default")
      (node (ref "IC1") (pin "13") (pinfunction "SDA_13") (pintype "bidirectional"))
      (node (ref "IC2") (pin "13") (pinfunction "SDA_13") (pintype "bidirectional"))
      (node (ref "IC3") (pin "13") (pinfunction "SDA_13") (pintype "bidirectional"))
      (node (ref "IC4") (pin "13") (pinfunction "SDA_13") (pintype "bidirectional"))
      (node (ref "IC5") (pin "13") (pinfunction "SDA_13") (pintype "bidirectional"))
      (node (ref "IC6") (pin "13") (pinfunction "SDA_13") (pintype "bidirectional"))
      (node (ref "IC7") (pin "15") (pinfunction "SDA_15") (pintype "bidirectional"))
      (node (ref "J1") (pin "2") (pinfunction "2_2") (pintype "passive"))
      (node (ref "J2") (pin "2") (pinfunction "2_2") (pintype "passive"))
    )
    (net (code "14") (name "/SS") (class "Default")
      (node (ref "IC7") (pin "4") (pinfunction "P0_4") (pintype "bidirectional"))
      (node (ref "J6") (pin "2") (pinfunction "2_2") (pintype "passive"))
      (node (ref "LEDSS") (pin "A") (pinfunction "A_A") (pintype "passive"))
    )
    (net (code "15") (name "/T1.1") (class "Default")
      (node (ref "T1.1") (pin "3") (pinfunction "C_3") (pintype "passive"))
      (node (ref "U$2") (pin "P$8") (pinfunction "7_P$8") (pintype "bidirectional"))
    )
    (net (code "16") (name "/T1.2") (class "Default")
      (node (ref "T1.2") (pin "3") (pinfunction "C_3") (pintype "passive"))
      (node (ref "U$2") (pin "P$9") (pinfunction "8_P$9") (pintype "bidirectional"))
    )
    (net (code "17") (name "/T1.3") (class "Default")
      (node (ref "T1.3") (pin "3") (pinfunction "C_3") (pintype "passive"))
    )
    (net (code "18") (name "/T1.4") (class "Default")
      (node (ref "T1.4") (pin "3") (pinfunction "C_3") (pintype "passive"))
      (node (ref "U$2") (pin "P$11") (pinfunction "9_P$11") (pintype "bidirectional"))
    )
    (net (code "19") (name "/T1.5") (class "Default")
      (node (ref "T1.5") (pin "3") (pinfunction "C_3") (pintype "passive"))
      (node (ref "U$2") (pin "P$12") (pinfunction "0_P$12") (pintype "bidirectional"))
    )
    (net (code "20") (name "/T1.6") (class "Default")
      (node (ref "T1.6") (pin "3") (pinfunction "C_3") (pintype "passive"))
      (node (ref "U$2") (pin "P$1") (pinfunction "1_P$1") (pintype "bidirectional"))
    )
    (net (code "21") (name "/T1.7") (class "Default")
      (node (ref "T1.7") (pin "3") (pinfunction "C_3") (pintype "passive"))
      (node (ref "U$2") (pin "P$2") (pinfunction "2_P$2") (pintype "bidirectional"))
    )
    (net (code "22") (name "/T1.8") (class "Default")
      (node (ref "T1.8") (pin "3") (pinfunction "C_3") (pintype "passive"))
      (node (ref "U$2") (pin "P$3") (pinfunction "3_P$3") (pintype "bidirectional"))
    )
    (net (code "23") (name "/T1.9") (class "Default")
      (node (ref "T1.9") (pin "3") (pinfunction "C_3") (pintype "passive"))
      (node (ref "U$2") (pin "P$7") (pinfunction "6_P$7") (pintype "bidirectional"))
    )
    (net (code "24") (name "/T1.10") (class "Default")
      (node (ref "T1.10") (pin "3") (pinfunction "C_3") (pintype "passive"))
      (node (ref "U$2") (pin "P$6") (pinfunction "5_P$6") (pintype "bidirectional"))
    )
    (net (code "25") (name "/T1.11") (class "Default")
      (node (ref "T1.11") (pin "3") (pinfunction "C_3") (pintype "passive"))
      (node (ref "U$2") (pin "P$5") (pinfunction "4_P$5") (pintype "bidirectional"))
    )
    (net (code "26") (name "/T2.1") (class "Default")
      (node (ref "T2.1") (pin "3") (pinfunction "C_3") (pintype "passive"))
      (node (ref "U$1") (pin "P$7") (pinfunction "6_P$7") (pintype "bidirectional"))
    )
    (net (code "27") (name "/T2.2") (class "Default")
      (node (ref "T2.2") (pin "3") (pinfunction "C_3") (pintype "passive"))
      (node (ref "U$1") (pin "P$6") (pinfunction "5_P$6") (pintype "bidirectional"))
    )
    (net (code "28") (name "/T2.3") (class "Default")
      (node (ref "T2.3") (pin "3") (pinfunction "C_3") (pintype "passive"))
      (node (ref "U$1") (pin "P$5") (pinfunction "4_P$5") (pintype "bidirectional"))
    )
    (net (code "29") (name "/T2.4") (class "Default")
      (node (ref "T2.4") (pin "3") (pinfunction "C_3") (pintype "passive"))
      (node (ref "U$1") (pin "P$3") (pinfunction "3_P$3") (pintype "bidirectional"))
    )
    (net (code "30") (name "/T2.5") (class "Default")
      (node (ref "T2.5") (pin "3") (pinfunction "C_3") (pintype "passive"))
      (node (ref "U$1") (pin "P$2") (pinfunction "2_P$2") (pintype "bidirectional"))
    )
    (net (code "31") (name "/T2.6") (class "Default")
      (node (ref "T2.6") (pin "3") (pinfunction "C_3") (pintype "passive"))
      (node (ref "U$1") (pin "P$1") (pinfunction "1_P$1") (pintype "bidirectional"))
    )
    (net (code "32") (name "/T2.7") (class "Default")
      (node (ref "T2.7") (pin "3") (pinfunction "C_3") (pintype "passive"))
      (node (ref "U$1") (pin "P$12") (pinfunction "0_P$12") (pintype "bidirectional"))
    )
    (net (code "33") (name "/T2.8") (class "Default")
      (node (ref "T2.8") (pin "3") (pinfunction "C_3") (pintype "passive"))
      (node (ref "U$1") (pin "P$11") (pinfunction "9_P$11") (pintype "bidirectional"))
    )
    (net (code "34") (name "/T2.9") (class "Default")
      (node (ref "T2.9") (pin "3") (pinfunction "C_3") (pintype "passive"))
      (node (ref "U$1") (pin "P$8") (pinfunction "7_P$8") (pintype "bidirectional"))
    )
    (net (code "35") (name "/T2.10") (class "Default")
      (node (ref "T2.10") (pin "3") (pinfunction "C_3") (pintype "passive"))
      (node (ref "U$1") (pin "P$9") (pinfunction "8_P$9") (pintype "bidirectional"))
    )
    (net (code "36") (name "/T2.11") (class "Default")
      (node (ref "T2.11") (pin "3") (pinfunction "C_3") (pintype "passive"))
    )
    (net (code "37") (name "/T3.1") (class "Default")
      (node (ref "T3.1") (pin "3") (pinfunction "C_3") (pintype "passive"))
      (node (ref "U$3") (pin "P$8") (pinfunction "7_P$8") (pintype "bidirectional"))
    )
    (net (code "38") (name "/T3.2") (class "Default")
      (node (ref "T3.2") (pin "3") (pinfunction "C_3") (pintype "passive"))
      (node (ref "U$3") (pin "P$9") (pinfunction "8_P$9") (pintype "bidirectional"))
    )
    (net (code "39") (name "/T3.3") (class "Default")
      (node (ref "T3.3") (pin "3") (pinfunction "C_3") (pintype "passive"))
    )
    (net (code "40") (name "/T3.4") (class "Default")
      (node (ref "T3.4") (pin "3") (pinfunction "C_3") (pintype "passive"))
      (node (ref "U$3") (pin "P$11") (pinfunction "9_P$11") (pintype "bidirectional"))
    )
    (net (code "41") (name "/T3.5") (class "Default")
      (node (ref "T3.5") (pin "3") (pinfunction "C_3") (pintype "passive"))
      (node (ref "U$3") (pin "P$12") (pinfunction "0_P$12") (pintype "bidirectional"))
    )
    (net (code "42") (name "/T3.6") (class "Default")
      (node (ref "T3.6") (pin "3") (pinfunction "C_3") (pintype "passive"))
      (node (ref "U$3") (pin "P$1") (pinfunction "1_P$1") (pintype "bidirectional"))
    )
    (net (code "43") (name "/T3.7") (class "Default")
      (node (ref "T3.7") (pin "3") (pinfunction "C_3") (pintype "passive"))
      (node (ref "U$3") (pin "P$2") (pinfunction "2_P$2") (pintype "bidirectional"))
    )
    (net (code "44") (name "/T3.8") (class "Default")
      (node (ref "T3.8") (pin "3") (pinfunction "C_3") (pintype "passive"))
      (node (ref "U$3") (pin "P$3") (pinfunction "3_P$3") (pintype "bidirectional"))
    )
    (net (code "45") (name "/T3.9") (class "Default")
      (node (ref "T3.9") (pin "3") (pinfunction "C_3") (pintype "passive"))
      (node (ref "U$3") (pin "P$7") (pinfunction "6_P$7") (pintype "bidirectional"))
    )
    (net (code "46") (name "/T3.10") (class "Default")
      (node (ref "T3.10") (pin "3") (pinfunction "C_3") (pintype "passive"))
      (node (ref "U$3") (pin "P$6") (pinfunction "5_P$6") (pintype "bidirectional"))
    )
    (net (code "47") (name "/T3.11") (class "Default")
      (node (ref "T3.11") (pin "3") (pinfunction "C_3") (pintype "passive"))
      (node (ref "U$3") (pin "P$5") (pinfunction "4_P$5") (pintype "bidirectional"))
    )
    (net (code "48") (name "/T4.1") (class "Default")
      (node (ref "T4.1") (pin "3") (pinfunction "C_3") (pintype "passive"))
      (node (ref "U$4") (pin "P$7") (pinfunction "6_P$7") (pintype "bidirectional"))
    )
    (net (code "49") (name "/T4.2") (class "Default")
      (node (ref "T4.2") (pin "3") (pinfunction "C_3") (pintype "passive"))
      (node (ref "U$4") (pin "P$6") (pinfunction "5_P$6") (pintype "bidirectional"))
    )
    (net (code "50") (name "/T4.3") (class "Default")
      (node (ref "T4.3") (pin "3") (pinfunction "C_3") (pintype "passive"))
      (node (ref "U$4") (pin "P$5") (pinfunction "4_P$5") (pintype "bidirectional"))
    )
    (net (code "51") (name "/T4.4") (class "Default")
      (node (ref "T.4.4") (pin "3") (pinfunction "C_3") (pintype "passive"))
      (node (ref "U$4") (pin "P$3") (pinfunction "3_P$3") (pintype "bidirectional"))
    )
    (net (code "52") (name "/T4.5") (class "Default")
      (node (ref "T4.5") (pin "3") (pinfunction "C_3") (pintype "passive"))
      (node (ref "U$4") (pin "P$2") (pinfunction "2_P$2") (pintype "bidirectional"))
    )
    (net (code "53") (name "/T4.6") (class "Default")
      (node (ref "T4.6") (pin "3") (pinfunction "C_3") (pintype "passive"))
      (node (ref "U$4") (pin "P$1") (pinfunction "1_P$1") (pintype "bidirectional"))
    )
    (net (code "54") (name "/T4.7") (class "Default")
      (node (ref "T4.7") (pin "3") (pinfunction "C_3") (pintype "passive"))
      (node (ref "U$4") (pin "P$12") (pinfunction "0_P$12") (pintype "bidirectional"))
    )
    (net (code "55") (name "/T4.8") (class "Default")
      (node (ref "T4.8") (pin "3") (pinfunction "C_3") (pintype "passive"))
      (node (ref "U$4") (pin "P$11") (pinfunction "9_P$11") (pintype "bidirectional"))
    )
    (net (code "56") (name "/T4.9") (class "Default")
      (node (ref "T4.9") (pin "3") (pinfunction "C_3") (pintype "passive"))
      (node (ref "U$4") (pin "P$8") (pinfunction "7_P$8") (pintype "bidirectional"))
    )
    (net (code "57") (name "/T4.10") (class "Default")
      (node (ref "T4.10") (pin "3") (pinfunction "C_3") (pintype "passive"))
      (node (ref "U$4") (pin "P$9") (pinfunction "8_P$9") (pintype "bidirectional"))
    )
    (net (code "58") (name "/T4.11") (class "Default")
      (node (ref "T4.11") (pin "3") (pinfunction "C_3") (pintype "passive"))
    )
    (net (code "59") (name "/T5.1") (class "Default")
      (node (ref "T5.1") (pin "3") (pinfunction "C_3") (pintype "passive"))
      (node (ref "U$5") (pin "P$8") (pinfunction "7_P$8") (pintype "bidirectional"))
    )
    (net (code "60") (name "/T5.2") (class "Default")
      (node (ref "T5.2") (pin "3") (pinfunction "C_3") (pintype "passive"))
      (node (ref "U$5") (pin "P$9") (pinfunction "8_P$9") (pintype "bidirectional"))
    )
    (net (code "61") (name "/T5.3") (class "Default")
      (node (ref "T5.3") (pin "3") (pinfunction "C_3") (pintype "passive"))
    )
    (net (code "62") (name "/T5.4") (class "Default")
      (node (ref "T5.4") (pin "3") (pinfunction "C_3") (pintype "passive"))
      (node (ref "U$5") (pin "P$11") (pinfunction "9_P$11") (pintype "bidirectional"))
    )
    (net (code "63") (name "/T5.5") (class "Default")
      (node (ref "T5.5") (pin "3") (pinfunction "C_3") (pintype "passive"))
      (node (ref "U$5") (pin "P$12") (pinfunction "0_P$12") (pintype "bidirectional"))
    )
    (net (code "64") (name "/T5.6") (class "Default")
      (node (ref "T5.6") (pin "3") (pinfunction "C_3") (pintype "passive"))
      (node (ref "U$5") (pin "P$1") (pinfunction "1_P$1") (pintype "bidirectional"))
    )
    (net (code "65") (name "/T5.7") (class "Default")
      (node (ref "T5.7") (pin "3") (pinfunction "C_3") (pintype "passive"))
      (node (ref "U$5") (pin "P$2") (pinfunction "2_P$2") (pintype "bidirectional"))
    )
    (net (code "66") (name "/T5.8") (class "Default")
      (node (ref "T5.8") (pin "3") (pinfunction "C_3") (pintype "passive"))
      (node (ref "U$5") (pin "P$3") (pinfunction "3_P$3") (pintype "bidirectional"))
    )
    (net (code "67") (name "/T5.9") (class "Default")
      (node (ref "T5.9") (pin "3") (pinfunction "C_3") (pintype "passive"))
      (node (ref "U$5") (pin "P$7") (pinfunction "6_P$7") (pintype "bidirectional"))
    )
    (net (code "68") (name "/T5.10") (class "Default")
      (node (ref "T5.10") (pin "3") (pinfunction "C_3") (pintype "passive"))
      (node (ref "U$5") (pin "P$6") (pinfunction "5_P$6") (pintype "bidirectional"))
    )
    (net (code "69") (name "/T5.11") (class "Default")
      (node (ref "T5.11") (pin "3") (pinfunction "C_3") (pintype "passive"))
      (node (ref "U$5") (pin "P$5") (pinfunction "4_P$5") (pintype "bidirectional"))
    )
    (net (code "70") (name "/T6.1") (class "Default")
      (node (ref "T6.1") (pin "3") (pinfunction "C_3") (pintype "passive"))
      (node (ref "U$6") (pin "P$7") (pinfunction "6_P$7") (pintype "bidirectional"))
    )
    (net (code "71") (name "/T6.2") (class "Default")
      (node (ref "T6.2") (pin "3") (pinfunction "C_3") (pintype "passive"))
      (node (ref "U$6") (pin "P$6") (pinfunction "5_P$6") (pintype "bidirectional"))
    )
    (net (code "72") (name "/T6.3") (class "Default")
      (node (ref "T6.3") (pin "3") (pinfunction "C_3") (pintype "passive"))
      (node (ref "U$6") (pin "P$5") (pinfunction "4_P$5") (pintype "bidirectional"))
    )
    (net (code "73") (name "/T6.4") (class "Default")
      (node (ref "T6.4") (pin "3") (pinfunction "C_3") (pintype "passive"))
      (node (ref "U$6") (pin "P$3") (pinfunction "3_P$3") (pintype "bidirectional"))
    )
    (net (code "74") (name "/T6.5") (class "Default")
      (node (ref "T6.5") (pin "3") (pinfunction "C_3") (pintype "passive"))
      (node (ref "U$6") (pin "P$2") (pinfunction "2_P$2") (pintype "bidirectional"))
    )
    (net (code "75") (name "/T6.6") (class "Default")
      (node (ref "T6.6") (pin "3") (pinfunction "C_3") (pintype "passive"))
      (node (ref "U$6") (pin "P$1") (pinfunction "1_P$1") (pintype "bidirectional"))
    )
    (net (code "76") (name "/T6.7") (class "Default")
      (node (ref "T6.7") (pin "3") (pinfunction "C_3") (pintype "passive"))
      (node (ref "U$6") (pin "P$12") (pinfunction "0_P$12") (pintype "bidirectional"))
    )
    (net (code "77") (name "/T6.8") (class "Default")
      (node (ref "T6.8") (pin "3") (pinfunction "C_3") (pintype "passive"))
      (node (ref "U$6") (pin "P$11") (pinfunction "9_P$11") (pintype "bidirectional"))
    )
    (net (code "78") (name "/T6.9") (class "Default")
      (node (ref "T6.9") (pin "3") (pinfunction "C_3") (pintype "passive"))
      (node (ref "U$6") (pin "P$8") (pinfunction "7_P$8") (pintype "bidirectional"))
    )
    (net (code "79") (name "/T6.10") (class "Default")
      (node (ref "T6.10") (pin "3") (pinfunction "C_3") (pintype "passive"))
      (node (ref "U$6") (pin "P$9") (pinfunction "8_P$9") (pintype "bidirectional"))
    )
    (net (code "80") (name "/T6.11") (class "Default")
      (node (ref "T6.11") (pin "3") (pinfunction "C_3") (pintype "passive"))
    )
    (net (code "81") (name "GND") (class "Default")
      (node (ref "C1") (pin "2") (pinfunction "2_2") (pintype "passive"))
      (node (ref "C11") (pin "2") (pinfunction "2_2") (pintype "passive"))
      (node (ref "C12") (pin "2") (pinfunction "2_2") (pintype "passive"))
      (node (ref "C3") (pin "2") (pinfunction "2_2") (pintype "passive"))
      (node (ref "C4") (pin "2") (pinfunction "2_2") (pintype "passive"))
      (node (ref "C7") (pin "2") (pinfunction "2_2") (pintype "passive"))
      (node (ref "C8") (pin "2") (pinfunction "2_2") (pintype "passive"))
      (node (ref "IC1") (pin "10") (pinfunction "VSS_10") (pintype "power_in"))
      (node (ref "IC1") (pin "15") (pinfunction "A0_15") (pintype "input"))
      (node (ref "IC1") (pin "5") (pinfunction "GPB4_5") (pintype "bidirectional"))
      (node (ref "IC1") (pin "6") (pinfunction "GPB5_6") (pintype "bidirectional"))
      (node (ref "IC1") (pin "7") (pinfunction "GPB6_7") (pintype "bidirectional"))
      (node (ref "IC2") (pin "10") (pinfunction "VSS_10") (pintype "power_in"))
      (node (ref "IC2") (pin "5") (pinfunction "GPB4_5") (pintype "bidirectional"))
      (node (ref "IC2") (pin "6") (pinfunction "GPB5_6") (pintype "bidirectional"))
      (node (ref "IC2") (pin "7") (pinfunction "GPB6_7") (pintype "bidirectional"))
      (node (ref "IC2") (pin "8") (pinfunction "GPB7_8") (pintype "bidirectional"))
      (node (ref "IC3") (pin "10") (pinfunction "VSS_10") (pintype "power_in"))
      (node (ref "IC3") (pin "15") (pinfunction "A0_15") (pintype "input"))
      (node (ref "IC3") (pin "17") (pinfunction "A2_17") (pintype "input"))
      (node (ref "IC3") (pin "5") (pinfunction "GPB4_5") (pintype "bidirectional"))
      (node (ref "IC3") (pin "6") (pinfunction "GPB5_6") (pintype "bidirectional"))
      (node (ref "IC3") (pin "7") (pinfunction "GPB6_7") (pintype "bidirectional"))
      (node (ref "IC3") (pin "8") (pinfunction "GPB7_8") (pintype "bidirectional"))
      (node (ref "IC4") (pin "10") (pinfunction "VSS_10") (pintype "power_in"))
      (node (ref "IC4") (pin "17") (pinfunction "A2_17") (pintype "input"))
      (node (ref "IC4") (pin "5") (pinfunction "GPB4_5") (pintype "bidirectional"))
      (node (ref "IC4") (pin "6") (pinfunction "GPB5_6") (pintype "bidirectional"))
      (node (ref "IC4") (pin "7") (pinfunction "GPB6_7") (pintype "bidirectional"))
      (node (ref "IC4") (pin "8") (pinfunction "GPB7_8") (pintype "bidirectional"))
      (node (ref "IC5") (pin "10") (pinfunction "VSS_10") (pintype "power_in"))
      (node (ref "IC5") (pin "15") (pinfunction "A0_15") (pintype "input"))
      (node (ref "IC5") (pin "16") (pinfunction "A1_16") (pintype "input"))
      (node (ref "IC5") (pin "17") (pinfunction "A2_17") (pintype "input"))
      (node (ref "IC5") (pin "5") (pinfunction "GPB4_5") (pintype "bidirectional"))
      (node (ref "IC5") (pin "6") (pinfunction "GPB5_6") (pintype "bidirectional"))
      (node (ref "IC5") (pin "7") (pinfunction "GPB6_7") (pintype "bidirectional"))
      (node (ref "IC5") (pin "8") (pinfunction "GPB7_8") (pintype "bidirectional"))
      (node (ref "IC6") (pin "10") (pinfunction "VSS_10") (pintype "power_in"))
      (node (ref "IC6") (pin "16") (pinfunction "A1_16") (pintype "input"))
      (node (ref "IC6") (pin "17") (pinfunction "A2_17") (pintype "input"))
      (node (ref "IC6") (pin "5") (pinfunction "GPB4_5") (pintype "bidirectional"))
      (node (ref "IC6") (pin "6") (pinfunction "GPB5_6") (pintype "bidirectional"))
      (node (ref "IC6") (pin "7") (pinfunction "GPB6_7") (pintype "bidirectional"))
      (node (ref "IC6") (pin "8") (pinfunction "GPB7_8") (pintype "bidirectional"))
      (node (ref "IC7") (pin "1") (pinfunction "A0_1") (pintype "input"))
      (node (ref "IC7") (pin "2") (pinfunction "A1_2") (pintype "input"))
      (node (ref "IC7") (pin "3") (pinfunction "A2_3") (pintype "input"))
      (node (ref "IC7") (pin "8") (pinfunction "VSS_8") (pintype "power_in"))
      (node (ref "J1") (pin "4") (pinfunction "4_4") (pintype "passive"))
      (node (ref "J2") (pin "4") (pinfunction "4_4") (pintype "passive"))
      (node (ref "J6") (pin "8") (pinfunction "8_8") (pintype "passive"))
      (node (ref "R2") (pin "1") (pinfunction "1_1") (pintype "passive"))
      (node (ref "R3") (pin "1") (pinfunction "1_1") (pintype "passive"))
      (node (ref "R4") (pin "1") (pinfunction "1_1") (pintype "passive"))
      (node (ref "R5") (pin "1") (pinfunction "1_1") (pintype "passive"))
      (node (ref "R6") (pin "1") (pinfunction "1_1") (pintype "passive"))
      (node (ref "R7") (pin "1") (pinfunction "1_1") (pintype "passive"))
      (node (ref "T.4.4") (pin "2") (pinfunction "E_2") (pintype "passive"))
      (node (ref "T1.1") (pin "2") (pinfunction "E_2") (pintype "passive"))
      (node (ref "T1.10") (pin "2") (pinfunction "E_2") (pintype "passive"))
      (node (ref "T1.11") (pin "2") (pinfunction "E_2") (pintype "passive"))
      (node (ref "T1.2") (pin "2") (pinfunction "E_2") (pintype "passive"))
      (node (ref "T1.3") (pin "2") (pinfunction "E_2") (pintype "passive"))
      (node (ref "T1.4") (pin "2") (pinfunction "E_2") (pintype "passive"))
      (node (ref "T1.5") (pin "2") (pinfunction "E_2") (pintype "passive"))
      (node (ref "T1.6") (pin "2") (pinfunction "E_2") (pintype "passive"))
      (node (ref "T1.7") (pin "2") (pinfunction "E_2") (pintype "passive"))
      (node (ref "T1.8") (pin "2") (pinfunction "E_2") (pintype "passive"))
      (node (ref "T1.9") (pin "2") (pinfunction "E_2") (pintype "passive"))
      (node (ref "T2.1") (pin "2") (pinfunction "E_2") (pintype "passive"))
      (node (ref "T2.10") (pin "2") (pinfunction "E_2") (pintype "passive"))
      (node (ref "T2.11") (pin "2") (pinfunction "E_2") (pintype "passive"))
      (node (ref "T2.2") (pin "2") (pinfunction "E_2") (pintype "passive"))
      (node (ref "T2.3") (pin "2") (pinfunction "E_2") (pintype "passive"))
      (node (ref "T2.4") (pin "2") (pinfunction "E_2") (pintype "passive"))
      (node (ref "T2.5") (pin "2") (pinfunction "E_2") (pintype "passive"))
      (node (ref "T2.7") (pin "2") (pinfunction "E_2") (pintype "passive"))
      (node (ref "T2.8") (pin "2") (pinfunction "E_2") (pintype "passive"))
      (node (ref "T2.9") (pin "2") (pinfunction "E_2") (pintype "passive"))
      (node (ref "T3.1") (pin "2") (pinfunction "E_2") (pintype "passive"))
      (node (ref "T3.10") (pin "2") (pinfunction "E_2") (pintype "passive"))
      (node (ref "T3.11") (pin "2") (pinfunction "E_2") (pintype "passive"))
      (node (ref "T3.2") (pin "2") (pinfunction "E_2") (pintype "passive"))
      (node (ref "T3.3") (pin "2") (pinfunction "E_2") (pintype "passive"))
      (node (ref "T3.4") (pin "2") (pinfunction "E_2") (pintype "passive"))
      (node (ref "T3.5") (pin "2") (pinfunction "E_2") (pintype "passive"))
      (node (ref "T3.6") (pin "2") (pinfunction "E_2") (pintype "passive"))
      (node (ref "T3.7") (pin "2") (pinfunction "E_2") (pintype "passive"))
      (node (ref "T3.8") (pin "2") (pinfunction "E_2") (pintype "passive"))
      (node (ref "T3.9") (pin "2") (pinfunction "E_2") (pintype "passive"))
      (node (ref "T4.1") (pin "2") (pinfunction "E_2") (pintype "passive"))
      (node (ref "T4.10") (pin "2") (pinfunction "E_2") (pintype "passive"))
      (node (ref "T4.11") (pin "2") (pinfunction "E_2") (pintype "passive"))
      (node (ref "T4.2") (pin "2") (pinfunction "E_2") (pintype "passive"))
      (node (ref "T4.3") (pin "2") (pinfunction "E_2") (pintype "passive"))
      (node (ref "T4.5") (pin "2") (pinfunction "E_2") (pintype "passive"))
      (node (ref "T4.6") (pin "2") (pinfunction "E_2") (pintype "passive"))
      (node (ref "T4.7") (pin "2") (pinfunction "E_2") (pintype "passive"))
      (node (ref "T4.8") (pin "2") (pinfunction "E_2") (pintype "passive"))
      (node (ref "T4.9") (pin "2") (pinfunction "E_2") (pintype "passive"))
      (node (ref "T5.1") (pin "2") (pinfunction "E_2") (pintype "passive"))
      (node (ref "T5.10") (pin "2") (pinfunction "E_2") (pintype "passive"))
      (node (ref "T5.11") (pin "2") (pinfunction "E_2") (pintype "passive"))
      (node (ref "T5.2") (pin "2") (pinfunction "E_2") (pintype "passive"))
      (node (ref "T5.3") (pin "2") (pinfunction "E_2") (pintype "passive"))
      (node (ref "T5.4") (pin "2") (pinfunction "E_2") (pintype "passive"))
      (node (ref "T5.5") (pin "2") (pinfunction "E_2") (pintype "passive"))
      (node (ref "T5.6") (pin "2") (pinfunction "E_2") (pintype "passive"))
      (node (ref "T5.7") (pin "2") (pinfunction "E_2") (pintype "passive"))
      (node (ref "T5.8") (pin "2") (pinfunction "E_2") (pintype "passive"))
      (node (ref "T5.9") (pin "2") (pinfunction "E_2") (pintype "passive"))
      (node (ref "T6.1") (pin "2") (pinfunction "E_2") (pintype "passive"))
      (node (ref "T6.10") (pin "2") (pinfunction "E_2") (pintype "passive"))
      (node (ref "T6.11") (pin "2") (pinfunction "E_2") (pintype "passive"))
      (node (ref "T6.2") (pin "2") (pinfunction "E_2") (pintype "passive"))
      (node (ref "T6.3") (pin "2") (pinfunction "E_2") (pintype "passive"))
      (node (ref "T6.4") (pin "2") (pinfunction "E_2") (pintype "passive"))
      (node (ref "T6.5") (pin "2") (pinfunction "E_2") (pintype "passive"))
      (node (ref "T6.6") (pin "2") (pinfunction "E_2") (pintype "passive"))
      (node (ref "T6.7") (pin "2") (pinfunction "E_2") (pintype "passive"))
      (node (ref "T6.8") (pin "2") (pinfunction "E_2") (pintype "passive"))
      (node (ref "T6.9") (pin "2") (pinfunction "E_2") (pintype "passive"))
    )
    (net (code "82") (name "Net-(IC1-GPA0)") (class "Default")
      (node (ref "IC1") (pin "21") (pinfunction "GPA0_21") (pintype "bidirectional"))
      (node (ref "R5.1") (pin "2") (pinfunction "2_2") (pintype "passive"))
    )
    (net (code "83") (name "Net-(IC1-GPA1)") (class "Default")
      (node (ref "IC1") (pin "22") (pinfunction "GPA1_22") (pintype "bidirectional"))
      (node (ref "R5.2") (pin "2") (pinfunction "2_2") (pintype "passive"))
    )
    (net (code "84") (name "Net-(IC1-GPA2)") (class "Default")
      (node (ref "IC1") (pin "23") (pinfunction "GPA2_23") (pintype "bidirectional"))
      (node (ref "R5.3") (pin "2") (pinfunction "2_2") (pintype "passive"))
    )
    (net (code "85") (name "Net-(IC1-GPA3)") (class "Default")
      (node (ref "IC1") (pin "24") (pinfunction "GPA3_24") (pintype "bidirectional"))
      (node (ref "R5.4") (pin "2") (pinfunction "2_2") (pintype "passive"))
    )
    (net (code "86") (name "Net-(IC1-GPA4)") (class "Default")
      (node (ref "IC1") (pin "25") (pinfunction "GPA4_25") (pintype "bidirectional"))
      (node (ref "R5.5") (pin "2") (pinfunction "2_2") (pintype "passive"))
    )
    (net (code "87") (name "Net-(IC1-GPA5)") (class "Default")
      (node (ref "IC1") (pin "26") (pinfunction "GPA5_26") (pintype "bidirectional"))
      (node (ref "R5.6") (pin "2") (pinfunction "2_2") (pintype "passive"))
    )
    (net (code "88") (name "Net-(IC1-GPA6)") (class "Default")
      (node (ref "IC1") (pin "27") (pinfunction "GPA6_27") (pintype "bidirectional"))
      (node (ref "R5.7") (pin "2") (pinfunction "2_2") (pintype "passive"))
    )
    (net (code "89") (name "Net-(IC1-GPA7)") (class "Default")
      (node (ref "IC1") (pin "28") (pinfunction "GPA7_28") (pintype "bidirectional"))
      (node (ref "R5.8") (pin "2") (pinfunction "2_2") (pintype "passive"))
    )
    (net (code "90") (name "Net-(IC1-GPB0)") (class "Default")
      (node (ref "IC1") (pin "1") (pinfunction "GPB0_1") (pintype "bidirectional"))
      (node (ref "R5.9") (pin "2") (pinfunction "2_2") (pintype "passive"))
    )
    (net (code "91") (name "Net-(IC1-GPB1)") (class "Default")
      (node (ref "IC1") (pin "2") (pinfunction "GPB1_2") (pintype "bidirectional"))
      (node (ref "R5.10") (pin "2") (pinfunction "2_2") (pintype "passive"))
    )
    (net (code "92") (name "Net-(IC1-GPB2)") (class "Default")
      (node (ref "IC1") (pin "3") (pinfunction "GPB2_3") (pintype "bidirectional"))
      (node (ref "R5.11") (pin "2") (pinfunction "2_2") (pintype "passive"))
    )
    (net (code "93") (name "Net-(IC2-GPA0)") (class "Default")
      (node (ref "IC2") (pin "21") (pinfunction "GPA0_21") (pintype "bidirectional"))
      (node (ref "R6.1") (pin "2") (pinfunction "2_2") (pintype "passive"))
    )
    (net (code "94") (name "Net-(IC2-GPA1)") (class "Default")
      (node (ref "IC2") (pin "22") (pinfunction "GPA1_22") (pintype "bidirectional"))
      (node (ref "R6.2") (pin "2") (pinfunction "2_2") (pintype "passive"))
    )
    (net (code "95") (name "Net-(IC2-GPA2)") (class "Default")
      (node (ref "IC2") (pin "23") (pinfunction "GPA2_23") (pintype "bidirectional"))
      (node (ref "R6.3") (pin "2") (pinfunction "2_2") (pintype "passive"))
    )
    (net (code "96") (name "Net-(IC2-GPA3)") (class "Default")
      (node (ref "IC2") (pin "24") (pinfunction "GPA3_24") (pintype "bidirectional"))
      (node (ref "R6.4") (pin "2") (pinfunction "2_2") (pintype "passive"))
    )
    (net (code "97") (name "Net-(IC2-GPA4)") (class "Default")
      (node (ref "IC2") (pin "25") (pinfunction "GPA4_25") (pintype "bidirectional"))
      (node (ref "R6.5") (pin "2") (pinfunction "2_2") (pintype "passive"))
    )
    (net (code "98") (name "Net-(IC2-GPA5)") (class "Default")
      (node (ref "IC2") (pin "26") (pinfunction "GPA5_26") (pintype "bidirectional"))
      (node (ref "R6.6") (pin "2") (pinfunction "2_2") (pintype "passive"))
    )
    (net (code "99") (name "Net-(IC2-GPA6)") (class "Default")
      (node (ref "IC2") (pin "27") (pinfunction "GPA6_27") (pintype "bidirectional"))
      (node (ref "R6.7") (pin "2") (pinfunction "2_2") (pintype "passive"))
    )
    (net (code "100") (name "Net-(IC2-GPA7)") (class "Default")
      (node (ref "IC2") (pin "28") (pinfunction "GPA7_28") (pintype "bidirectional"))
      (node (ref "R6.8") (pin "2") (pinfunction "2_2") (pintype "passive"))
    )
    (net (code "101") (name "Net-(IC2-GPB0)") (class "Default")
      (node (ref "IC2") (pin "1") (pinfunction "GPB0_1") (pintype "bidirectional"))
      (node (ref "R6.9") (pin "2") (pinfunction "2_2") (pintype "passive"))
    )
    (net (code "102") (name "Net-(IC2-GPB1)") (class "Default")
      (node (ref "IC2") (pin "2") (pinfunction "GPB1_2") (pintype "bidirectional"))
      (node (ref "R6.10") (pin "2") (pinfunction "2_2") (pintype "passive"))
    )
    (net (code "103") (name "Net-(IC3-GPA0)") (class "Default")
      (node (ref "IC3") (pin "21") (pinfunction "GPA0_21") (pintype "bidirectional"))
      (node (ref "R3.1") (pin "2") (pinfunction "2_2") (pintype "passive"))
    )
    (net (code "104") (name "Net-(IC3-GPA1)") (class "Default")
      (node (ref "IC3") (pin "22") (pinfunction "GPA1_22") (pintype "bidirectional"))
      (node (ref "R3.2") (pin "2") (pinfunction "2_2") (pintype "passive"))
    )
    (net (code "105") (name "Net-(IC3-GPA2)") (class "Default")
      (node (ref "IC3") (pin "23") (pinfunction "GPA2_23") (pintype "bidirectional"))
      (node (ref "R3.3") (pin "2") (pinfunction "2_2") (pintype "passive"))
    )
    (net (code "106") (name "Net-(IC3-GPA3)") (class "Default")
      (node (ref "IC3") (pin "24") (pinfunction "GPA3_24") (pintype "bidirectional"))
      (node (ref "R3.4") (pin "2") (pinfunction "2_2") (pintype "passive"))
    )
    (net (code "107") (name "Net-(IC3-GPA4)") (class "Default")
      (node (ref "IC3") (pin "25") (pinfunction "GPA4_25") (pintype "bidirectional"))
      (node (ref "R3.5") (pin "2") (pinfunction "2_2") (pintype "passive"))
    )
    (net (code "108") (name "Net-(IC3-GPA5)") (class "Default")
      (node (ref "IC3") (pin "26") (pinfunction "GPA5_26") (pintype "bidirectional"))
      (node (ref "R3.6") (pin "2") (pinfunction "2_2") (pintype "passive"))
    )
    (net (code "109") (name "Net-(IC3-GPA6)") (class "Default")
      (node (ref "IC3") (pin "27") (pinfunction "GPA6_27") (pintype "bidirectional"))
      (node (ref "R3.7") (pin "2") (pinfunction "2_2") (pintype "passive"))
    )
    (net (code "110") (name "Net-(IC3-GPA7)") (class "Default")
      (node (ref "IC3") (pin "28") (pinfunction "GPA7_28") (pintype "bidirectional"))
      (node (ref "R3.8") (pin "2") (pinfunction "2_2") (pintype "passive"))
    )
    (net (code "111") (name "Net-(IC3-GPB0)") (class "Default")
      (node (ref "IC3") (pin "1") (pinfunction "GPB0_1") (pintype "bidirectional"))
      (node (ref "R3.9") (pin "2") (pinfunction "2_2") (pintype "passive"))
    )
    (net (code "112") (name "Net-(IC3-GPB1)") (class "Default")
      (node (ref "IC3") (pin "2") (pinfunction "GPB1_2") (pintype "bidirectional"))
      (node (ref "R3.10") (pin "2") (pinfunction "2_2") (pintype "passive"))
    )
    (net (code "113") (name "Net-(IC4-GPA0)") (class "Default")
      (node (ref "IC4") (pin "21") (pinfunction "GPA0_21") (pintype "bidirectional"))
      (node (ref "R4.1") (pin "2") (pinfunction "2_2") (pintype "passive"))
    )
    (net (code "114") (name "Net-(IC4-GPA1)") (class "Default")
      (node (ref "IC4") (pin "22") (pinfunction "GPA1_22") (pintype "bidirectional"))
      (node (ref "R4.2") (pin "2") (pinfunction "2_2") (pintype "passive"))
    )
    (net (code "115") (name "Net-(IC4-GPA2)") (class "Default")
      (node (ref "IC4") (pin "23") (pinfunction "GPA2_23") (pintype "bidirectional"))
      (node (ref "R4.3") (pin "2") (pinfunction "2_2") (pintype "passive"))
    )
    (net (code "116") (name "Net-(IC4-GPA3)") (class "Default")
      (node (ref "IC4") (pin "24") (pinfunction "GPA3_24") (pintype "bidirectional"))
      (node (ref "R4.4") (pin "2") (pinfunction "2_2") (pintype "passive"))
    )
    (net (code "117") (name "Net-(IC4-GPA4)") (class "Default")
      (node (ref "IC4") (pin "25") (pinfunction "GPA4_25") (pintype "bidirectional"))
      (node (ref "R4.5") (pin "2") (pinfunction "2_2") (pintype "passive"))
    )
    (net (code "118") (name "Net-(IC4-GPA5)") (class "Default")
      (node (ref "IC4") (pin "26") (pinfunction "GPA5_26") (pintype "bidirectional"))
      (node (ref "R4.6") (pin "2") (pinfunction "2_2") (pintype "passive"))
    )
    (net (code "119") (name "Net-(IC4-GPA6)") (class "Default")
      (node (ref "IC4") (pin "27") (pinfunction "GPA6_27") (pintype "bidirectional"))
      (node (ref "R4.7") (pin "2") (pinfunction "2_2") (pintype "passive"))
    )
    (net (code "120") (name "Net-(IC4-GPA7)") (class "Default")
      (node (ref "IC4") (pin "28") (pinfunction "GPA7_28") (pintype "bidirectional"))
      (node (ref "R4.8") (pin "2") (pinfunction "2_2") (pintype "passive"))
    )
    (net (code "121") (name "Net-(IC4-GPB0)") (class "Default")
      (node (ref "IC4") (pin "1") (pinfunction "GPB0_1") (pintype "bidirectional"))
      (node (ref "R4.9") (pin "2") (pinfunction "2_2") (pintype "passive"))
    )
    (net (code "122") (name "Net-(IC4-GPB1)") (class "Default")
      (node (ref "IC4") (pin "2") (pinfunction "GPB1_2") (pintype "bidirectional"))
      (node (ref "R4.10") (pin "2") (pinfunction "2_2") (pintype "passive"))
    )
    (net (code "123") (name "Net-(IC5-GPA0)") (class "Default")
      (node (ref "IC5") (pin "21") (pinfunction "GPA0_21") (pintype "bidirectional"))
      (node (ref "R1.1") (pin "2") (pinfunction "2_2") (pintype "passive"))
    )
    (net (code "124") (name "Net-(IC5-GPA1)") (class "Default")
      (node (ref "IC5") (pin "22") (pinfunction "GPA1_22") (pintype "bidirectional"))
      (node (ref "R1.2") (pin "2") (pinfunction "2_2") (pintype "passive"))
    )
    (net (code "125") (name "Net-(IC5-GPA2)") (class "Default")
      (node (ref "IC5") (pin "23") (pinfunction "GPA2_23") (pintype "bidirectional"))
      (node (ref "R1.3") (pin "2") (pinfunction "2_2") (pintype "passive"))
    )
    (net (code "126") (name "Net-(IC5-GPA3)") (class "Default")
      (node (ref "IC5") (pin "24") (pinfunction "GPA3_24") (pintype "bidirectional"))
      (node (ref "R1.4") (pin "2") (pinfunction "2_2") (pintype "passive"))
    )
    (net (code "127") (name "Net-(IC5-GPA4)") (class "Default")
      (node (ref "IC5") (pin "25") (pinfunction "GPA4_25") (pintype "bidirectional"))
      (node (ref "R1.5") (pin "2") (pinfunction "2_2") (pintype "passive"))
    )
    (net (code "128") (name "Net-(IC5-GPA5)") (class "Default")
      (node (ref "IC5") (pin "26") (pinfunction "GPA5_26") (pintype "bidirectional"))
      (node (ref "R1.6") (pin "2") (pinfunction "2_2") (pintype "passive"))
    )
    (net (code "129") (name "Net-(IC5-GPA6)") (class "Default")
      (node (ref "IC5") (pin "27") (pinfunction "GPA6_27") (pintype "bidirectional"))
      (node (ref "R1.7") (pin "2") (pinfunction "2_2") (pintype "passive"))
    )
    (net (code "130") (name "Net-(IC5-GPA7)") (class "Default")
      (node (ref "IC5") (pin "28") (pinfunction "GPA7_28") (pintype "bidirectional"))
      (node (ref "R1.8") (pin "2") (pinfunction "2_2") (pintype "passive"))
    )
    (net (code "131") (name "Net-(IC5-GPB0)") (class "Default")
      (node (ref "IC5") (pin "1") (pinfunction "GPB0_1") (pintype "bidirectional"))
      (node (ref "R1.9") (pin "2") (pinfunction "2_2") (pintype "passive"))
    )
    (net (code "132") (name "Net-(IC5-GPB1)") (class "Default")
      (node (ref "IC5") (pin "2") (pinfunction "GPB1_2") (pintype "bidirectional"))
      (node (ref "R1.10") (pin "2") (pinfunction "2_2") (pintype "passive"))
    )
    (net (code "133") (name "Net-(IC6-GPA0)") (class "Default")
      (node (ref "IC6") (pin "21") (pinfunction "GPA0_21") (pintype "bidirectional"))
      (node (ref "R2.1") (pin "2") (pinfunction "2_2") (pintype "passive"))
    )
    (net (code "134") (name "Net-(IC6-GPA1)") (class "Default")
      (node (ref "IC6") (pin "22") (pinfunction "GPA1_22") (pintype "bidirectional"))
      (node (ref "R2.2") (pin "2") (pinfunction "2_2") (pintype "passive"))
    )
    (net (code "135") (name "Net-(IC6-GPA2)") (class "Default")
      (node (ref "IC6") (pin "23") (pinfunction "GPA2_23") (pintype "bidirectional"))
      (node (ref "R2.3") (pin "2") (pinfunction "2_2") (pintype "passive"))
    )
    (net (code "136") (name "Net-(IC6-GPA3)") (class "Default")
      (node (ref "IC6") (pin "24") (pinfunction "GPA3_24") (pintype "bidirectional"))
      (node (ref "R2.4") (pin "2") (pinfunction "2_2") (pintype "passive"))
    )
    (net (code "137") (name "Net-(IC6-GPA4)") (class "Default")
      (node (ref "IC6") (pin "25") (pinfunction "GPA4_25") (pintype "bidirectional"))
      (node (ref "R2.5") (pin "2") (pinfunction "2_2") (pintype "passive"))
    )
    (net (code "138") (name "Net-(IC6-GPA5)") (class "Default")
      (node (ref "IC6") (pin "26") (pinfunction "GPA5_26") (pintype "bidirectional"))
      (node (ref "R2.6") (pin "2") (pinfunction "2_2") (pintype "passive"))
    )
    (net (code "139") (name "Net-(IC6-GPA6)") (class "Default")
      (node (ref "IC6") (pin "27") (pinfunction "GPA6_27") (pintype "bidirectional"))
      (node (ref "R2.7") (pin "2") (pinfunction "2_2") (pintype "passive"))
    )
    (net (code "140") (name "Net-(IC6-GPA7)") (class "Default")
      (node (ref "IC6") (pin "28") (pinfunction "GPA7_28") (pintype "bidirectional"))
      (node (ref "R2.8") (pin "2") (pinfunction "2_2") (pintype "passive"))
    )
    (net (code "141") (name "Net-(IC6-GPB0)") (class "Default")
      (node (ref "IC6") (pin "1") (pinfunction "GPB0_1") (pintype "bidirectional"))
      (node (ref "R2.9") (pin "2") (pinfunction "2_2") (pintype "passive"))
    )
    (net (code "142") (name "Net-(IC6-GPB1)") (class "Default")
      (node (ref "IC6") (pin "2") (pinfunction "GPB1_2") (pintype "bidirectional"))
      (node (ref "R2.10") (pin "2") (pinfunction "2_2") (pintype "passive"))
    )
    (net (code "143") (name "Net-(IC6-GPB2)") (class "Default")
      (node (ref "IC6") (pin "3") (pinfunction "GPB2_3") (pintype "bidirectional"))
      (node (ref "R2.11") (pin "2") (pinfunction "2_2") (pintype "passive"))
    )
    (net (code "144") (name "Net-(LEDH-PadC)") (class "Default")
      (node (ref "LEDH") (pin "C") (pinfunction "C_C") (pintype "passive"))
      (node (ref "R4") (pin "2") (pinfunction "2_2") (pintype "passive"))
    )
    (net (code "145") (name "Net-(LEDHH-PadC)") (class "Default")
      (node (ref "LEDHH") (pin "C") (pinfunction "C_C") (pintype "passive"))
      (node (ref "R3") (pin "2") (pinfunction "2_2") (pintype "passive"))
    )
    (net (code "146") (name "Net-(LEDM-PadC)") (class "Default")
      (node (ref "LEDM") (pin "C") (pinfunction "C_C") (pintype "passive"))
      (node (ref "R6") (pin "2") (pinfunction "2_2") (pintype "passive"))
    )
    (net (code "147") (name "Net-(LEDMM-PadC)") (class "Default")
      (node (ref "LEDMM") (pin "C") (pinfunction "C_C") (pintype "passive"))
      (node (ref "R5") (pin "2") (pinfunction "2_2") (pintype "passive"))
    )
    (net (code "148") (name "Net-(LEDS-PadC)") (class "Default")
      (node (ref "LEDS") (pin "C") (pinfunction "C_C") (pintype "passive"))
      (node (ref "R2") (pin "2") (pinfunction "2_2") (pintype "passive"))
    )
    (net (code "149") (name "Net-(LEDSS-PadC)") (class "Default")
      (node (ref "LEDSS") (pin "C") (pinfunction "C_C") (pintype "passive"))
      (node (ref "R7") (pin "2") (pinfunction "2_2") (pintype "passive"))
    )
    (net (code "150") (name "Net-(T.4.4-B)") (class "Default")
      (node (ref "R4.4") (pin "1") (pinfunction "1_1") (pintype "passive"))
      (node (ref "T.4.4") (pin "1") (pinfunction "B_1") (pintype "passive"))
    )
    (net (code "151") (name "Net-(T1.1-B)") (class "Default")
      (node (ref "R1.1") (pin "1") (pinfunction "1_1") (pintype "passive"))
      (node (ref "T1.1") (pin "1") (pinfunction "B_1") (pintype "passive"))
    )
    (net (code "152") (name "Net-(T1.2-B)") (class "Default")
      (node (ref "R1.2") (pin "1") (pinfunction "1_1") (pintype "passive"))
      (node (ref "T1.2") (pin "1") (pinfunction "B_1") (pintype "passive"))
    )
    (net (code "153") (name "Net-(T1.3-B)") (class "Default")
      (node (ref "R1.3") (pin "1") (pinfunction "1_1") (pintype "passive"))
      (node (ref "T1.3") (pin "1") (pinfunction "B_1") (pintype "passive"))
    )
    (net (code "154") (name "Net-(T1.4-B)") (class "Default")
      (node (ref "R1.4") (pin "1") (pinfunction "1_1") (pintype "passive"))
      (node (ref "T1.4") (pin "1") (pinfunction "B_1") (pintype "passive"))
    )
    (net (code "155") (name "Net-(T1.5-B)") (class "Default")
      (node (ref "R1.5") (pin "1") (pinfunction "1_1") (pintype "passive"))
      (node (ref "T1.5") (pin "1") (pinfunction "B_1") (pintype "passive"))
    )
    (net (code "156") (name "Net-(T1.6-B)") (class "Default")
      (node (ref "R1.6") (pin "1") (pinfunction "1_1") (pintype "passive"))
      (node (ref "T1.6") (pin "1") (pinfunction "B_1") (pintype "passive"))
    )
    (net (code "157") (name "Net-(T1.7-B)") (class "Default")
      (node (ref "R1.7") (pin "1") (pinfunction "1_1") (pintype "passive"))
      (node (ref "T1.7") (pin "1") (pinfunction "B_1") (pintype "passive"))
    )
    (net (code "158") (name "Net-(T1.8-B)") (class "Default")
      (node (ref "R1.8") (pin "1") (pinfunction "1_1") (pintype "passive"))
      (node (ref "T1.8") (pin "1") (pinfunction "B_1") (pintype "passive"))
    )
    (net (code "159") (name "Net-(T1.9-B)") (class "Default")
      (node (ref "R1.9") (pin "1") (pinfunction "1_1") (pintype "passive"))
      (node (ref "T1.9") (pin "1") (pinfunction "B_1") (pintype "passive"))
    )
    (net (code "160") (name "Net-(T1.10-B)") (class "Default")
      (node (ref "R1.10") (pin "1") (pinfunction "1_1") (pintype "passive"))
      (node (ref "T1.10") (pin "1") (pinfunction "B_1") (pintype "passive"))
    )
    (net (code "161") (name "Net-(T1.11-B)") (class "Default")
      (node (ref "R1.11") (pin "1") (pinfunction "1_1") (pintype "passive"))
      (node (ref "T1.11") (pin "1") (pinfunction "B_1") (pintype "passive"))
    )
    (net (code "162") (name "Net-(T2.1-B)") (class "Default")
      (node (ref "R2.1") (pin "1") (pinfunction "1_1") (pintype "passive"))
      (node (ref "T2.1") (pin "1") (pinfunction "B_1") (pintype "passive"))
    )
    (net (code "163") (name "Net-(T2.2-B)") (class "Default")
      (node (ref "R2.2") (pin "1") (pinfunction "1_1") (pintype "passive"))
      (node (ref "T2.2") (pin "1") (pinfunction "B_1") (pintype "passive"))
    )
    (net (code "164") (name "Net-(T2.3-B)") (class "Default")
      (node (ref "R2.3") (pin "1") (pinfunction "1_1") (pintype "passive"))
      (node (ref "T2.3") (pin "1") (pinfunction "B_1") (pintype "passive"))
    )
    (net (code "165") (name "Net-(T2.4-B)") (class "Default")
      (node (ref "R2.4") (pin "1") (pinfunction "1_1") (pintype "passive"))
      (node (ref "T2.4") (pin "1") (pinfunction "B_1") (pintype "passive"))
    )
    (net (code "166") (name "Net-(T2.5-B)") (class "Default")
      (node (ref "R2.5") (pin "1") (pinfunction "1_1") (pintype "passive"))
      (node (ref "T2.5") (pin "1") (pinfunction "B_1") (pintype "passive"))
    )
    (net (code "167") (name "Net-(T2.6-B)") (class "Default")
      (node (ref "R2.6") (pin "1") (pinfunction "1_1") (pintype "passive"))
      (node (ref "T2.6") (pin "1") (pinfunction "B_1") (pintype "passive"))
    )
    (net (code "168") (name "Net-(T2.7-B)") (class "Default")
      (node (ref "R2.7") (pin "1") (pinfunction "1_1") (pintype "passive"))
      (node (ref "T2.7") (pin "1") (pinfunction "B_1") (pintype "passive"))
    )
    (net (code "169") (name "Net-(T2.8-B)") (class "Default")
      (node (ref "R2.8") (pin "1") (pinfunction "1_1") (pintype "passive"))
      (node (ref "T2.8") (pin "1") (pinfunction "B_1") (pintype "passive"))
    )
    (net (code "170") (name "Net-(T2.9-B)") (class "Default")
      (node (ref "R2.9") (pin "1") (pinfunction "1_1") (pintype "passive"))
      (node (ref "T2.9") (pin "1") (pinfunction "B_1") (pintype "passive"))
    )
    (net (code "171") (name "Net-(T2.10-B)") (class "Default")
      (node (ref "R2.10") (pin "1") (pinfunction "1_1") (pintype "passive"))
      (node (ref "T2.10") (pin "1") (pinfunction "B_1") (pintype "passive"))
    )
    (net (code "172") (name "Net-(T2.11-B)") (class "Default")
      (node (ref "R2.11") (pin "1") (pinfunction "1_1") (pintype "passive"))
      (node (ref "T2.11") (pin "1") (pinfunction "B_1") (pintype "passive"))
    )
    (net (code "173") (name "Net-(T3.1-B)") (class "Default")
      (node (ref "R3.1") (pin "1") (pinfunction "1_1") (pintype "passive"))
      (node (ref "T3.1") (pin "1") (pinfunction "B_1") (pintype "passive"))
    )
    (net (code "174") (name "Net-(T3.2-B)") (class "Default")
      (node (ref "R3.2") (pin "1") (pinfunction "1_1") (pintype "passive"))
      (node (ref "T3.2") (pin "1") (pinfunction "B_1") (pintype "passive"))
    )
    (net (code "175") (name "Net-(T3.3-B)") (class "Default")
      (node (ref "R3.3") (pin "1") (pinfunction "1_1") (pintype "passive"))
      (node (ref "T3.3") (pin "1") (pinfunction "B_1") (pintype "passive"))
    )
    (net (code "176") (name "Net-(T3.4-B)") (class "Default")
      (node (ref "R3.4") (pin "1") (pinfunction "1_1") (pintype "passive"))
      (node (ref "T3.4") (pin "1") (pinfunction "B_1") (pintype "passive"))
    )
    (net (code "177") (name "Net-(T3.5-B)") (class "Default")
      (node (ref "R3.5") (pin "1") (pinfunction "1_1") (pintype "passive"))
      (node (ref "T3.5") (pin "1") (pinfunction "B_1") (pintype "passive"))
    )
    (net (code "178") (name "Net-(T3.6-B)") (class "Default")
      (node (ref "R3.6") (pin "1") (pinfunction "1_1") (pintype "passive"))
      (node (ref "T3.6") (pin "1") (pinfunction "B_1") (pintype "passive"))
    )
    (net (code "179") (name "Net-(T3.7-B)") (class "Default")
      (node (ref "R3.7") (pin "1") (pinfunction "1_1") (pintype "passive"))
      (node (ref "T3.7") (pin "1") (pinfunction "B_1") (pintype "passive"))
    )
    (net (code "180") (name "Net-(T3.8-B)") (class "Default")
      (node (ref "R3.8") (pin "1") (pinfunction "1_1") (pintype "passive"))
      (node (ref "T3.8") (pin "1") (pinfunction "B_1") (pintype "passive"))
    )
    (net (code "181") (name "Net-(T3.9-B)") (class "Default")
      (node (ref "R3.9") (pin "1") (pinfunction "1_1") (pintype "passive"))
      (node (ref "T3.9") (pin "1") (pinfunction "B_1") (pintype "passive"))
    )
    (net (code "182") (name "Net-(T3.10-B)") (class "Default")
      (node (ref "R3.10") (pin "1") (pinfunction "1_1") (pintype "passive"))
      (node (ref "T3.10") (pin "1") (pinfunction "B_1") (pintype "passive"))
    )
    (net (code "183") (name "Net-(T3.11-B)") (class "Default")
      (node (ref "R3.11") (pin "1") (pinfunction "1_1") (pintype "passive"))
      (node (ref "T3.11") (pin "1") (pinfunction "B_1") (pintype "passive"))
    )
    (net (code "184") (name "Net-(T4.1-B)") (class "Default")
      (node (ref "R4.1") (pin "1") (pinfunction "1_1") (pintype "passive"))
      (node (ref "T4.1") (pin "1") (pinfunction "B_1") (pintype "passive"))
    )
    (net (code "185") (name "Net-(T4.2-B)") (class "Default")
      (node (ref "R4.2") (pin "1") (pinfunction "1_1") (pintype "passive"))
      (node (ref "T4.2") (pin "1") (pinfunction "B_1") (pintype "passive"))
    )
    (net (code "186") (name "Net-(T4.3-B)") (class "Default")
      (node (ref "R4.3") (pin "1") (pinfunction "1_1") (pintype "passive"))
      (node (ref "T4.3") (pin "1") (pinfunction "B_1") (pintype "passive"))
    )
    (net (code "187") (name "Net-(T4.5-B)") (class "Default")
      (node (ref "R4.5") (pin "1") (pinfunction "1_1") (pintype "passive"))
      (node (ref "T4.5") (pin "1") (pinfunction "B_1") (pintype "passive"))
    )
    (net (code "188") (name "Net-(T4.6-B)") (class "Default")
      (node (ref "R4.6") (pin "1") (pinfunction "1_1") (pintype "passive"))
      (node (ref "T4.6") (pin "1") (pinfunction "B_1") (pintype "passive"))
    )
    (net (code "189") (name "Net-(T4.7-B)") (class "Default")
      (node (ref "R4.7") (pin "1") (pinfunction "1_1") (pintype "passive"))
      (node (ref "T4.7") (pin "1") (pinfunction "B_1") (pintype "passive"))
    )
    (net (code "190") (name "Net-(T4.8-B)") (class "Default")
      (node (ref "R4.8") (pin "1") (pinfunction "1_1") (pintype "passive"))
      (node (ref "T4.8") (pin "1") (pinfunction "B_1") (pintype "passive"))
    )
    (net (code "191") (name "Net-(T4.9-B)") (class "Default")
      (node (ref "R4.9") (pin "1") (pinfunction "1_1") (pintype "passive"))
      (node (ref "T4.9") (pin "1") (pinfunction "B_1") (pintype "passive"))
    )
    (net (code "192") (name "Net-(T4.10-B)") (class "Default")
      (node (ref "R4.10") (pin "1") (pinfunction "1_1") (pintype "passive"))
      (node (ref "T4.10") (pin "1") (pinfunction "B_1") (pintype "passive"))
    )
    (net (code "193") (name "Net-(T4.11-B)") (class "Default")
      (node (ref "R4.11") (pin "1") (pinfunction "1_1") (pintype "passive"))
      (node (ref "T4.11") (pin "1") (pinfunction "B_1") (pintype "passive"))
    )
    (net (code "194") (name "Net-(T5.1-B)") (class "Default")
      (node (ref "R5.1") (pin "1") (pinfunction "1_1") (pintype "passive"))
      (node (ref "T5.1") (pin "1") (pinfunction "B_1") (pintype "passive"))
    )
    (net (code "195") (name "Net-(T5.2-B)") (class "Default")
      (node (ref "R5.2") (pin "1") (pinfunction "1_1") (pintype "passive"))
      (node (ref "T5.2") (pin "1") (pinfunction "B_1") (pintype "passive"))
    )
    (net (code "196") (name "Net-(T5.3-B)") (class "Default")
      (node (ref "R5.3") (pin "1") (pinfunction "1_1") (pintype "passive"))
      (node (ref "T5.3") (pin "1") (pinfunction "B_1") (pintype "passive"))
    )
    (net (code "197") (name "Net-(T5.4-B)") (class "Default")
      (node (ref "R5.4") (pin "1") (pinfunction "1_1") (pintype "passive"))
      (node (ref "T5.4") (pin "1") (pinfunction "B_1") (pintype "passive"))
    )
    (net (code "198") (name "Net-(T5.5-B)") (class "Default")
      (node (ref "R5.5") (pin "1") (pinfunction "1_1") (pintype "passive"))
      (node (ref "T5.5") (pin "1") (pinfunction "B_1") (pintype "passive"))
    )
    (net (code "199") (name "Net-(T5.6-B)") (class "Default")
      (node (ref "R5.6") (pin "1") (pinfunction "1_1") (pintype "passive"))
      (node (ref "T5.6") (pin "1") (pinfunction "B_1") (pintype "passive"))
    )
    (net (code "200") (name "Net-(T5.7-B)") (class "Default")
      (node (ref "R5.7") (pin "1") (pinfunction "1_1") (pintype "passive"))
      (node (ref "T5.7") (pin "1") (pinfunction "B_1") (pintype "passive"))
    )
    (net (code "201") (name "Net-(T5.8-B)") (class "Default")
      (node (ref "R5.8") (pin "1") (pinfunction "1_1") (pintype "passive"))
      (node (ref "T5.8") (pin "1") (pinfunction "B_1") (pintype "passive"))
    )
    (net (code "202") (name "Net-(T5.9-B)") (class "Default")
      (node (ref "R5.9") (pin "1") (pinfunction "1_1") (pintype "passive"))
      (node (ref "T5.9") (pin "1") (pinfunction "B_1") (pintype "passive"))
    )
    (net (code "203") (name "Net-(T5.10-B)") (class "Default")
      (node (ref "R5.10") (pin "1") (pinfunction "1_1") (pintype "passive"))
      (node (ref "T5.10") (pin "1") (pinfunction "B_1") (pintype "passive"))
    )
    (net (code "204") (name "Net-(T5.11-B)") (class "Default")
      (node (ref "R5.11") (pin "1") (pinfunction "1_1") (pintype "passive"))
      (node (ref "T5.11") (pin "1") (pinfunction "B_1") (pintype "passive"))
    )
    (net (code "205") (name "Net-(T6.1-B)") (class "Default")
      (node (ref "R6.1") (pin "1") (pinfunction "1_1") (pintype "passive"))
      (node (ref "T6.1") (pin "1") (pinfunction "B_1") (pintype "passive"))
    )
    (net (code "206") (name "Net-(T6.2-B)") (class "Default")
      (node (ref "R6.2") (pin "1") (pinfunction "1_1") (pintype "passive"))
      (node (ref "T6.2") (pin "1") (pinfunction "B_1") (pintype "passive"))
    )
    (net (code "207") (name "Net-(T6.3-B)") (class "Default")
      (node (ref "R6.3") (pin "1") (pinfunction "1_1") (pintype "passive"))
      (node (ref "T6.3") (pin "1") (pinfunction "B_1") (pintype "passive"))
    )
    (net (code "208") (name "Net-(T6.4-B)") (class "Default")
      (node (ref "R6.4") (pin "1") (pinfunction "1_1") (pintype "passive"))
      (node (ref "T6.4") (pin "1") (pinfunction "B_1") (pintype "passive"))
    )
    (net (code "209") (name "Net-(T6.5-B)") (class "Default")
      (node (ref "R6.5") (pin "1") (pinfunction "1_1") (pintype "passive"))
      (node (ref "T6.5") (pin "1") (pinfunction "B_1") (pintype "passive"))
    )
    (net (code "210") (name "Net-(T6.6-B)") (class "Default")
      (node (ref "R6.6") (pin "1") (pinfunction "1_1") (pintype "passive"))
      (node (ref "T6.6") (pin "1") (pinfunction "B_1") (pintype "passive"))
    )
    (net (code "211") (name "Net-(T6.7-B)") (class "Default")
      (node (ref "R6.7") (pin "1") (pinfunction "1_1") (pintype "passive"))
      (node (ref "T6.7") (pin "1") (pinfunction "B_1") (pintype "passive"))
    )
    (net (code "212") (name "Net-(T6.8-B)") (class "Default")
      (node (ref "R6.8") (pin "1") (pinfunction "1_1") (pintype "passive"))
      (node (ref "T6.8") (pin "1") (pinfunction "B_1") (pintype "passive"))
    )
    (net (code "213") (name "Net-(T6.9-B)") (class "Default")
      (node (ref "R6.9") (pin "1") (pinfunction "1_1") (pintype "passive"))
      (node (ref "T6.9") (pin "1") (pinfunction "B_1") (pintype "passive"))
    )
    (net (code "214") (name "Net-(T6.10-B)") (class "Default")
      (node (ref "R6.10") (pin "1") (pinfunction "1_1") (pintype "passive"))
      (node (ref "T6.10") (pin "1") (pinfunction "B_1") (pintype "passive"))
    )
    (net (code "215") (name "Net-(T6.11-B)") (class "Default")
      (node (ref "R6.11") (pin "1") (pinfunction "1_1") (pintype "passive"))
      (node (ref "T6.11") (pin "1") (pinfunction "B_1") (pintype "passive"))
    )
    (net (code "216") (name "Net-(U$1-A)") (class "Default")
      (node (ref "RA1") (pin "2") (pinfunction "2_2") (pintype "passive"))
      (node (ref "U$1") (pin "P$13") (pinfunction "A_P$13") (pintype "bidirectional"))
    )
    (net (code "217") (name "Net-(U$2-A)") (class "Default")
      (node (ref "RA2") (pin "2") (pinfunction "2_2") (pintype "passive"))
      (node (ref "U$2") (pin "P$13") (pinfunction "A_P$13") (pintype "bidirectional"))
    )
    (net (code "218") (name "Net-(U$3-A)") (class "Default")
      (node (ref "RA4") (pin "2") (pinfunction "2_2") (pintype "passive"))
      (node (ref "U$3") (pin "P$13") (pinfunction "A_P$13") (pintype "bidirectional"))
    )
    (net (code "219") (name "Net-(U$4-A)") (class "Default")
      (node (ref "RA3") (pin "2") (pinfunction "2_2") (pintype "passive"))
      (node (ref "U$4") (pin "P$13") (pinfunction "A_P$13") (pintype "bidirectional"))
    )
    (net (code "220") (name "Net-(U$5-A)") (class "Default")
      (node (ref "RA6") (pin "2") (pinfunction "2_2") (pintype "passive"))
      (node (ref "U$5") (pin "P$13") (pinfunction "A_P$13") (pintype "bidirectional"))
    )
    (net (code "221") (name "Net-(U$6-A)") (class "Default")
      (node (ref "RA5") (pin "2") (pinfunction "2_2") (pintype "passive"))
      (node (ref "U$6") (pin "P$13") (pinfunction "A_P$13") (pintype "bidirectional"))
    )
    (net (code "222") (name "VCC") (class "Default")
      (node (ref "C1") (pin "1") (pinfunction "1_1") (pintype "passive"))
      (node (ref "C11") (pin "1") (pinfunction "1_1") (pintype "passive"))
      (node (ref "C12") (pin "1") (pinfunction "1_1") (pintype "passive"))
      (node (ref "C3") (pin "1") (pinfunction "1_1") (pintype "passive"))
      (node (ref "C4") (pin "1") (pinfunction "1_1") (pintype "passive"))
      (node (ref "C7") (pin "1") (pinfunction "1_1") (pintype "passive"))
      (node (ref "C8") (pin "1") (pinfunction "1_1") (pintype "passive"))
      (node (ref "IC1") (pin "16") (pinfunction "A1_16") (pintype "input"))
      (node (ref "IC1") (pin "17") (pinfunction "A2_17") (pintype "input"))
      (node (ref "IC1") (pin "18") (pinfunction "~{RESET}_18") (pintype "input"))
      (node (ref "IC1") (pin "8") (pinfunction "GPB7_8") (pintype "bidirectional"))
      (node (ref "IC1") (pin "9") (pinfunction "VDD_9") (pintype "power_in"))
      (node (ref "IC2") (pin "15") (pinfunction "A0_15") (pintype "input"))
      (node (ref "IC2") (pin "16") (pinfunction "A1_16") (pintype "input"))
      (node (ref "IC2") (pin "17") (pinfunction "A2_17") (pintype "input"))
      (node (ref "IC2") (pin "18") (pinfunction "~{RESET}_18") (pintype "input"))
      (node (ref "IC2") (pin "9") (pinfunction "VDD_9") (pintype "power_in"))
      (node (ref "IC3") (pin "16") (pinfunction "A1_16") (pintype "input"))
      (node (ref "IC3") (pin "18") (pinfunction "~{RESET}_18") (pintype "input"))
      (node (ref "IC3") (pin "9") (pinfunction "VDD_9") (pintype "power_in"))
      (node (ref "IC4") (pin "15") (pinfunction "A0_15") (pintype "input"))
      (node (ref "IC4") (pin "16") (pinfunction "A1_16") (pintype "input"))
      (node (ref "IC4") (pin "18") (pinfunction "~{RESET}_18") (pintype "input"))
      (node (ref "IC4") (pin "9") (pinfunction "VDD_9") (pintype "power_in"))
      (node (ref "IC5") (pin "18") (pinfunction "~{RESET}_18") (pintype "input"))
      (node (ref "IC5") (pin "9") (pinfunction "VDD_9") (pintype "power_in"))
      (node (ref "IC6") (pin "15") (pinfunction "A0_15") (pintype "input"))
      (node (ref "IC6") (pin "18") (pinfunction "~{RESET}_18") (pintype "input"))
      (node (ref "IC6") (pin "9") (pinfunction "VDD_9") (pintype "power_in"))
      (node (ref "IC7") (pin "16") (pinfunction "VDD_16") (pintype "power_in"))
      (node (ref "J1") (pin "1") (pinfunction "1_1") (pintype "passive"))
      (node (ref "J2") (pin "1") (pinfunction "1_1") (pintype "passive"))
      (node (ref "J6") (pin "1") (pinfunction "1_1") (pintype "passive"))
    )
    (net (code "223") (name "unconnected-(IC1-GPB3-Pad4)") (class "Default")
      (node (ref "IC1") (pin "4") (pinfunction "GPB3_4") (pintype "bidirectional"))
    )
    (net (code "224") (name "unconnected-(IC1-INTA-Pad20)") (class "Default")
      (node (ref "IC1") (pin "20") (pinfunction "INTA_20") (pintype "output"))
    )
    (net (code "225") (name "unconnected-(IC1-INTB-Pad19)") (class "Default")
      (node (ref "IC1") (pin "19") (pinfunction "INTB_19") (pintype "output"))
    )
    (net (code "226") (name "unconnected-(IC2-GPB3-Pad4)") (class "Default")
      (node (ref "IC2") (pin "4") (pinfunction "GPB3_4") (pintype "bidirectional"))
    )
    (net (code "227") (name "unconnected-(IC2-INTA-Pad20)") (class "Default")
      (node (ref "IC2") (pin "20") (pinfunction "INTA_20") (pintype "output"))
    )
    (net (code "228") (name "unconnected-(IC2-INTB-Pad19)") (class "Default")
      (node (ref "IC2") (pin "19") (pinfunction "INTB_19") (pintype "output"))
    )
    (net (code "229") (name "unconnected-(IC3-GPB3-Pad4)") (class "Default")
      (node (ref "IC3") (pin "4") (pinfunction "GPB3_4") (pintype "bidirectional"))
    )
    (net (code "230") (name "unconnected-(IC3-INTA-Pad20)") (class "Default")
      (node (ref "IC3") (pin "20") (pinfunction "INTA_20") (pintype "output"))
    )
    (net (code "231") (name "unconnected-(IC3-INTB-Pad19)") (class "Default")
      (node (ref "IC3") (pin "19") (pinfunction "INTB_19") (pintype "output"))
    )
    (net (code "232") (name "unconnected-(IC4-GPB3-Pad4)") (class "Default")
      (node (ref "IC4") (pin "4") (pinfunction "GPB3_4") (pintype "bidirectional"))
    )
    (net (code "233") (name "unconnected-(IC4-INTA-Pad20)") (class "Default")
      (node (ref "IC4") (pin "20") (pinfunction "INTA_20") (pintype "output"))
    )
    (net (code "234") (name "unconnected-(IC4-INTB-Pad19)") (class "Default")
      (node (ref "IC4") (pin "19") (pinfunction "INTB_19") (pintype "output"))
    )
    (net (code "235") (name "unconnected-(IC5-GPB3-Pad4)") (class "Default")
      (node (ref "IC5") (pin "4") (pinfunction "GPB3_4") (pintype "bidirectional"))
    )
    (net (code "236") (name "unconnected-(IC5-INTA-Pad20)") (class "Default")
      (node (ref "IC5") (pin "20") (pinfunction "INTA_20") (pintype "output"))
    )
    (net (code "237") (name "unconnected-(IC5-INTB-Pad19)") (class "Default")
      (node (ref "IC5") (pin "19") (pinfunction "INTB_19") (pintype "output"))
    )
    (net (code "238") (name "unconnected-(IC6-GPB3-Pad4)") (class "Default")
      (node (ref "IC6") (pin "4") (pinfunction "GPB3_4") (pintype "bidirectional"))
    )
    (net (code "239") (name "unconnected-(IC6-INTA-Pad20)") (class "Default")
      (node (ref "IC6") (pin "20") (pinfunction "INTA_20") (pintype "output"))
    )
    (net (code "240") (name "unconnected-(IC6-INTB-Pad19)") (class "Default")
      (node (ref "IC6") (pin "19") (pinfunction "INTB_19") (pintype "output"))
    )
    (net (code "241") (name "unconnected-(IC7-P6-Pad11)") (class "Default")
      (node (ref "IC7") (pin "11") (pinfunction "P6_11") (pintype "bidirectional"))
    )
    (net (code "242") (name "unconnected-(IC7-P7-Pad12)") (class "Default")
      (node (ref "IC7") (pin "12") (pinfunction "P7_12") (pintype "bidirectional"))
    )
    (net (code "243") (name "unconnected-(J1-Pad6)") (class "Default")
      (node (ref "J1") (pin "6") (pinfunction "6_6") (pintype "passive"))
    )
    (net (code "244") (name "unconnected-(J2-Pad6)") (class "Default")
      (node (ref "J2") (pin "6") (pinfunction "6_6") (pintype "passive"))
    )
    (net (code "245") (name "unconnected-(T2.6-E-Pad2)") (class "Default")
      (node (ref "T2.6") (pin "2") (pinfunction "E_2") (pintype "passive"))
    )
    (net (code "246") (name "unconnected-(U$1-NC-PadP$4)") (class "Default")
      (node (ref "U$1") (pin "P$4") (pinfunction "NC_P$4") (pintype "bidirectional"))
    )
    (net (code "247") (name "unconnected-(U$2-NC-PadP$4)") (class "Default")
      (node (ref "U$2") (pin "P$4") (pinfunction "NC_P$4") (pintype "bidirectional"))
    )
    (net (code "248") (name "unconnected-(U$3-NC-PadP$4)") (class "Default")
      (node (ref "U$3") (pin "P$4") (pinfunction "NC_P$4") (pintype "bidirectional"))
    )
    (net (code "249") (name "unconnected-(U$4-NC-PadP$4)") (class "Default")
      (node (ref "U$4") (pin "P$4") (pinfunction "NC_P$4") (pintype "bidirectional"))
    )
    (net (code "250") (name "unconnected-(U$5-NC-PadP$4)") (class "Default")
      (node (ref "U$5") (pin "P$4") (pinfunction "NC_P$4") (pintype "bidirectional"))
    )
    (net (code "251") (name "unconnected-(U$6-NC-PadP$4)") (class "Default")
      (node (ref "U$6") (pin "P$4") (pinfunction "NC_P$4") (pintype "bidirectional"))
    )
  )
)
